# rev_n_v35.net
KiCad netlist of a schematic drawn in EAGLE
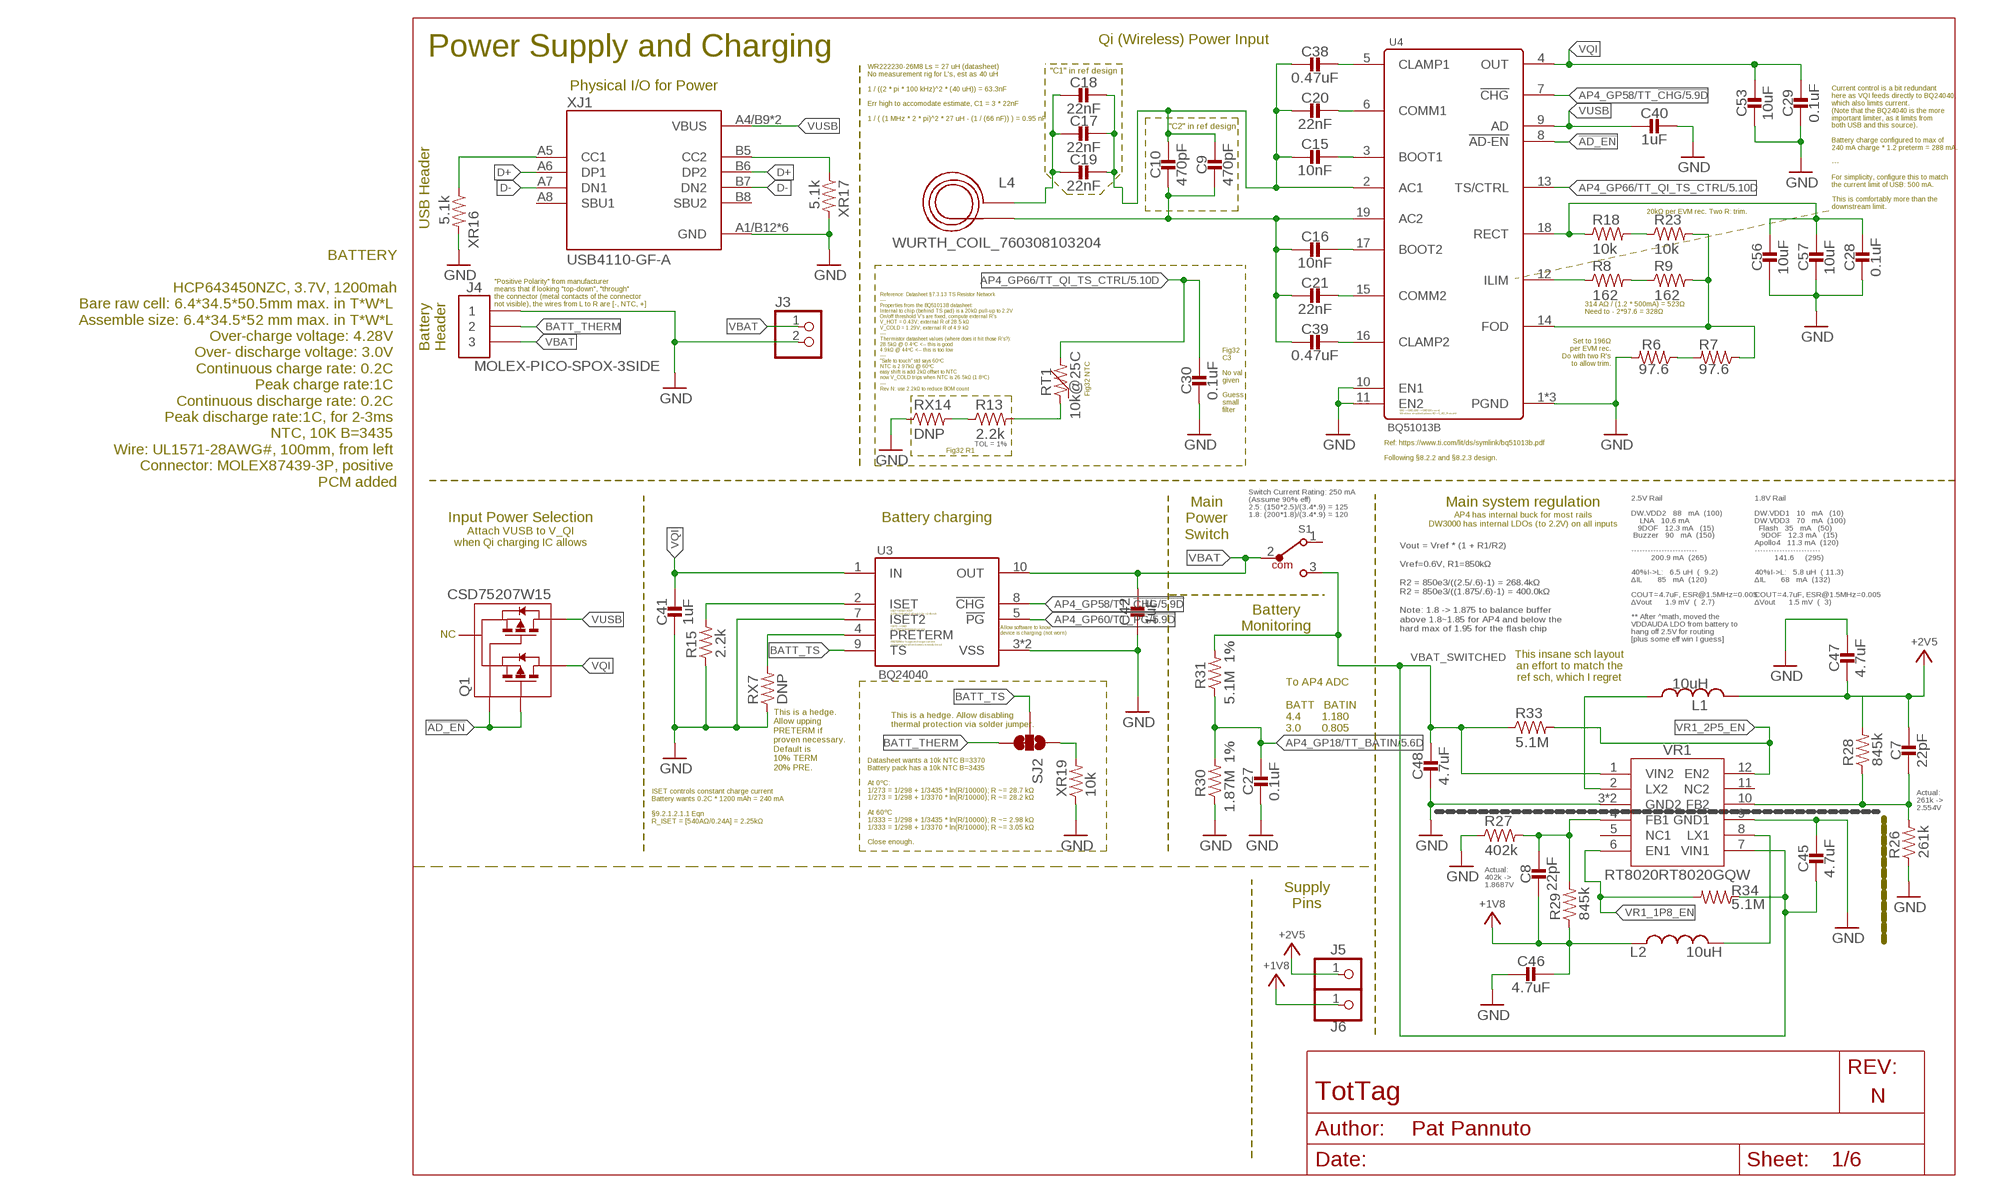
[diagram p0: schematic, sheet 1]
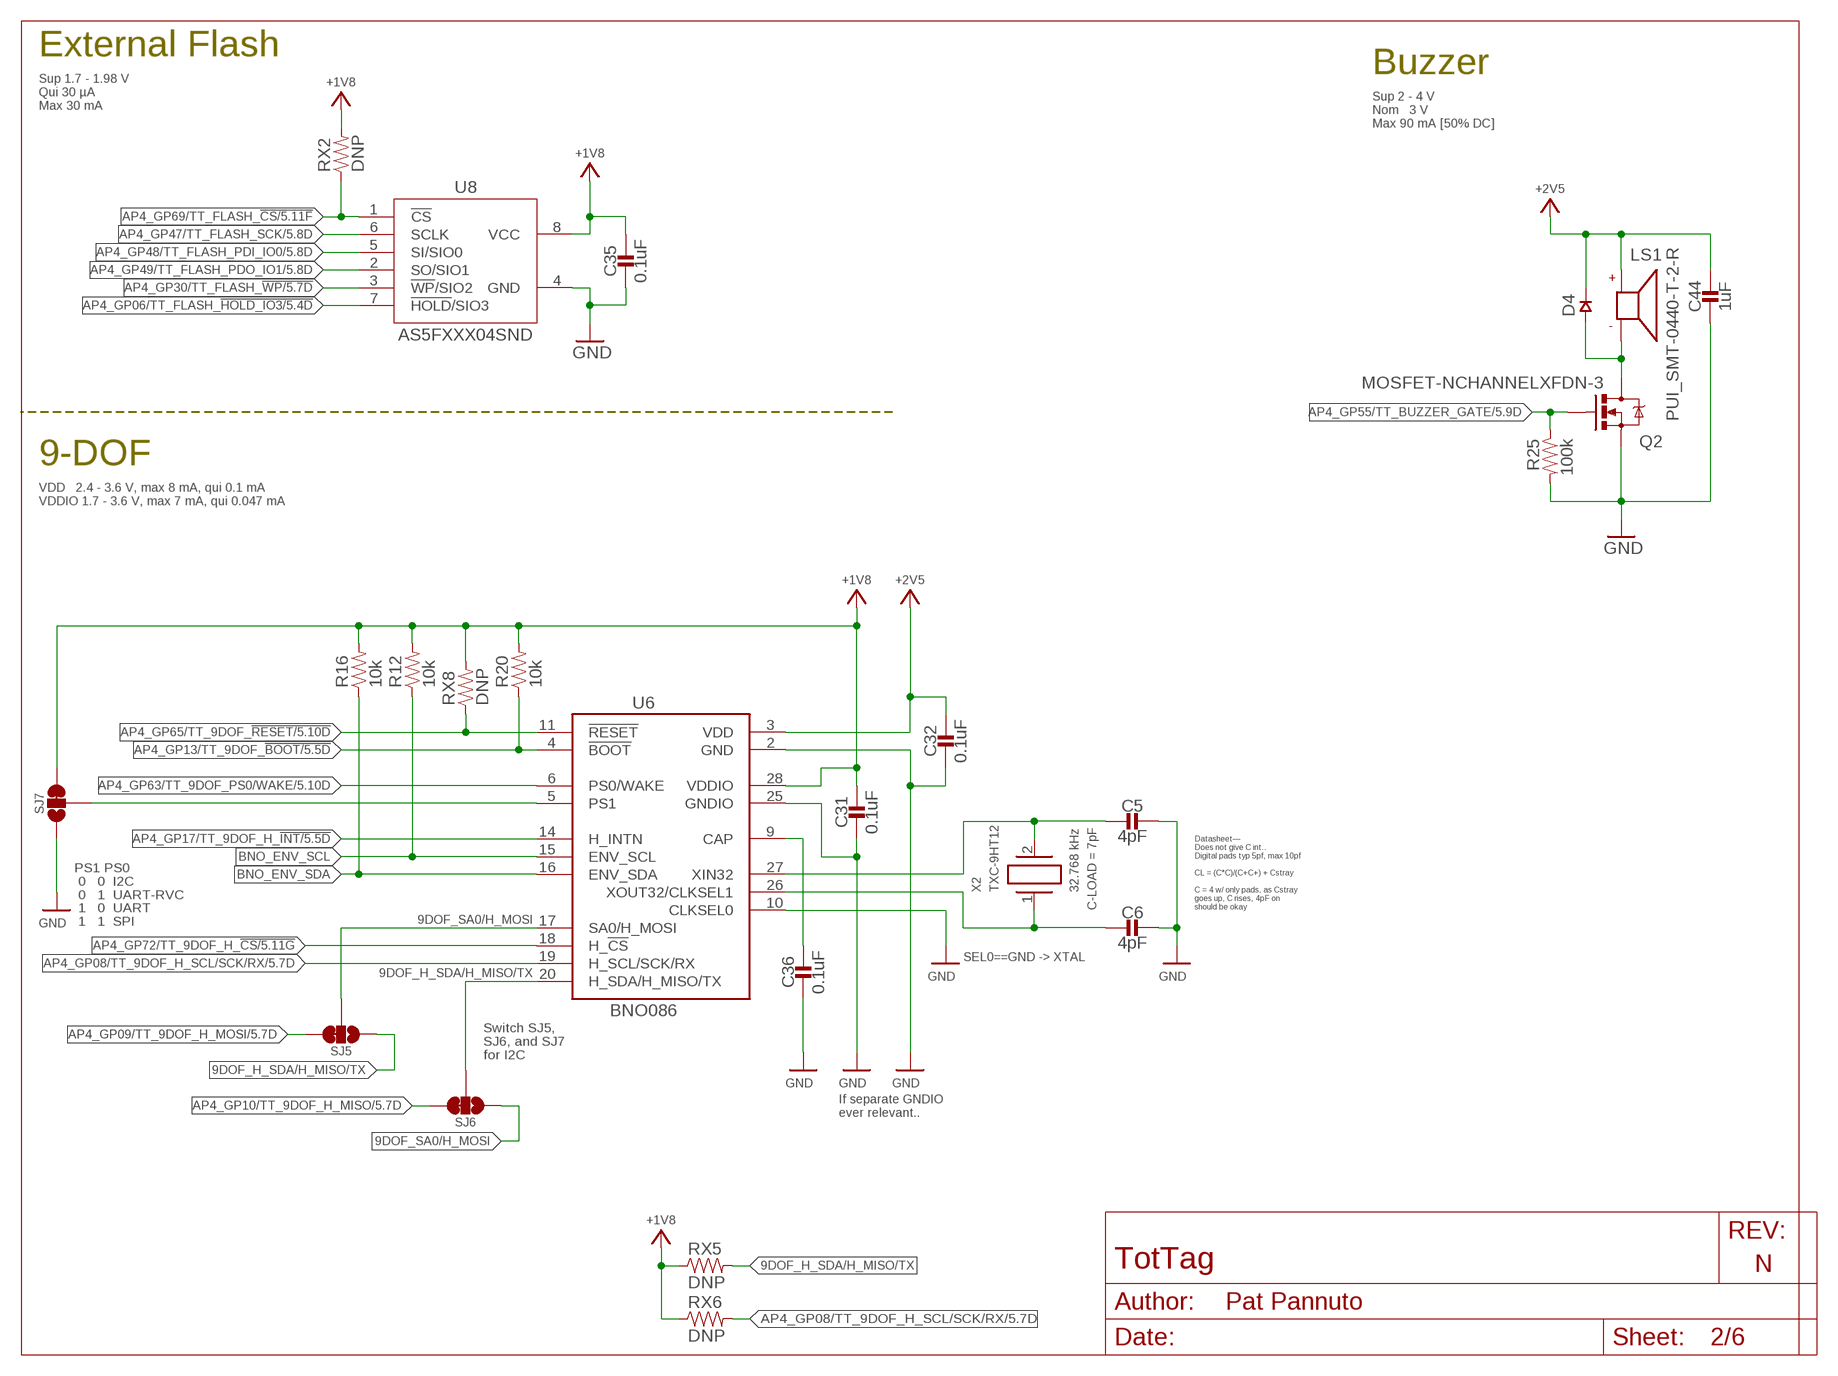
[diagram p1: schematic, sheet 2]
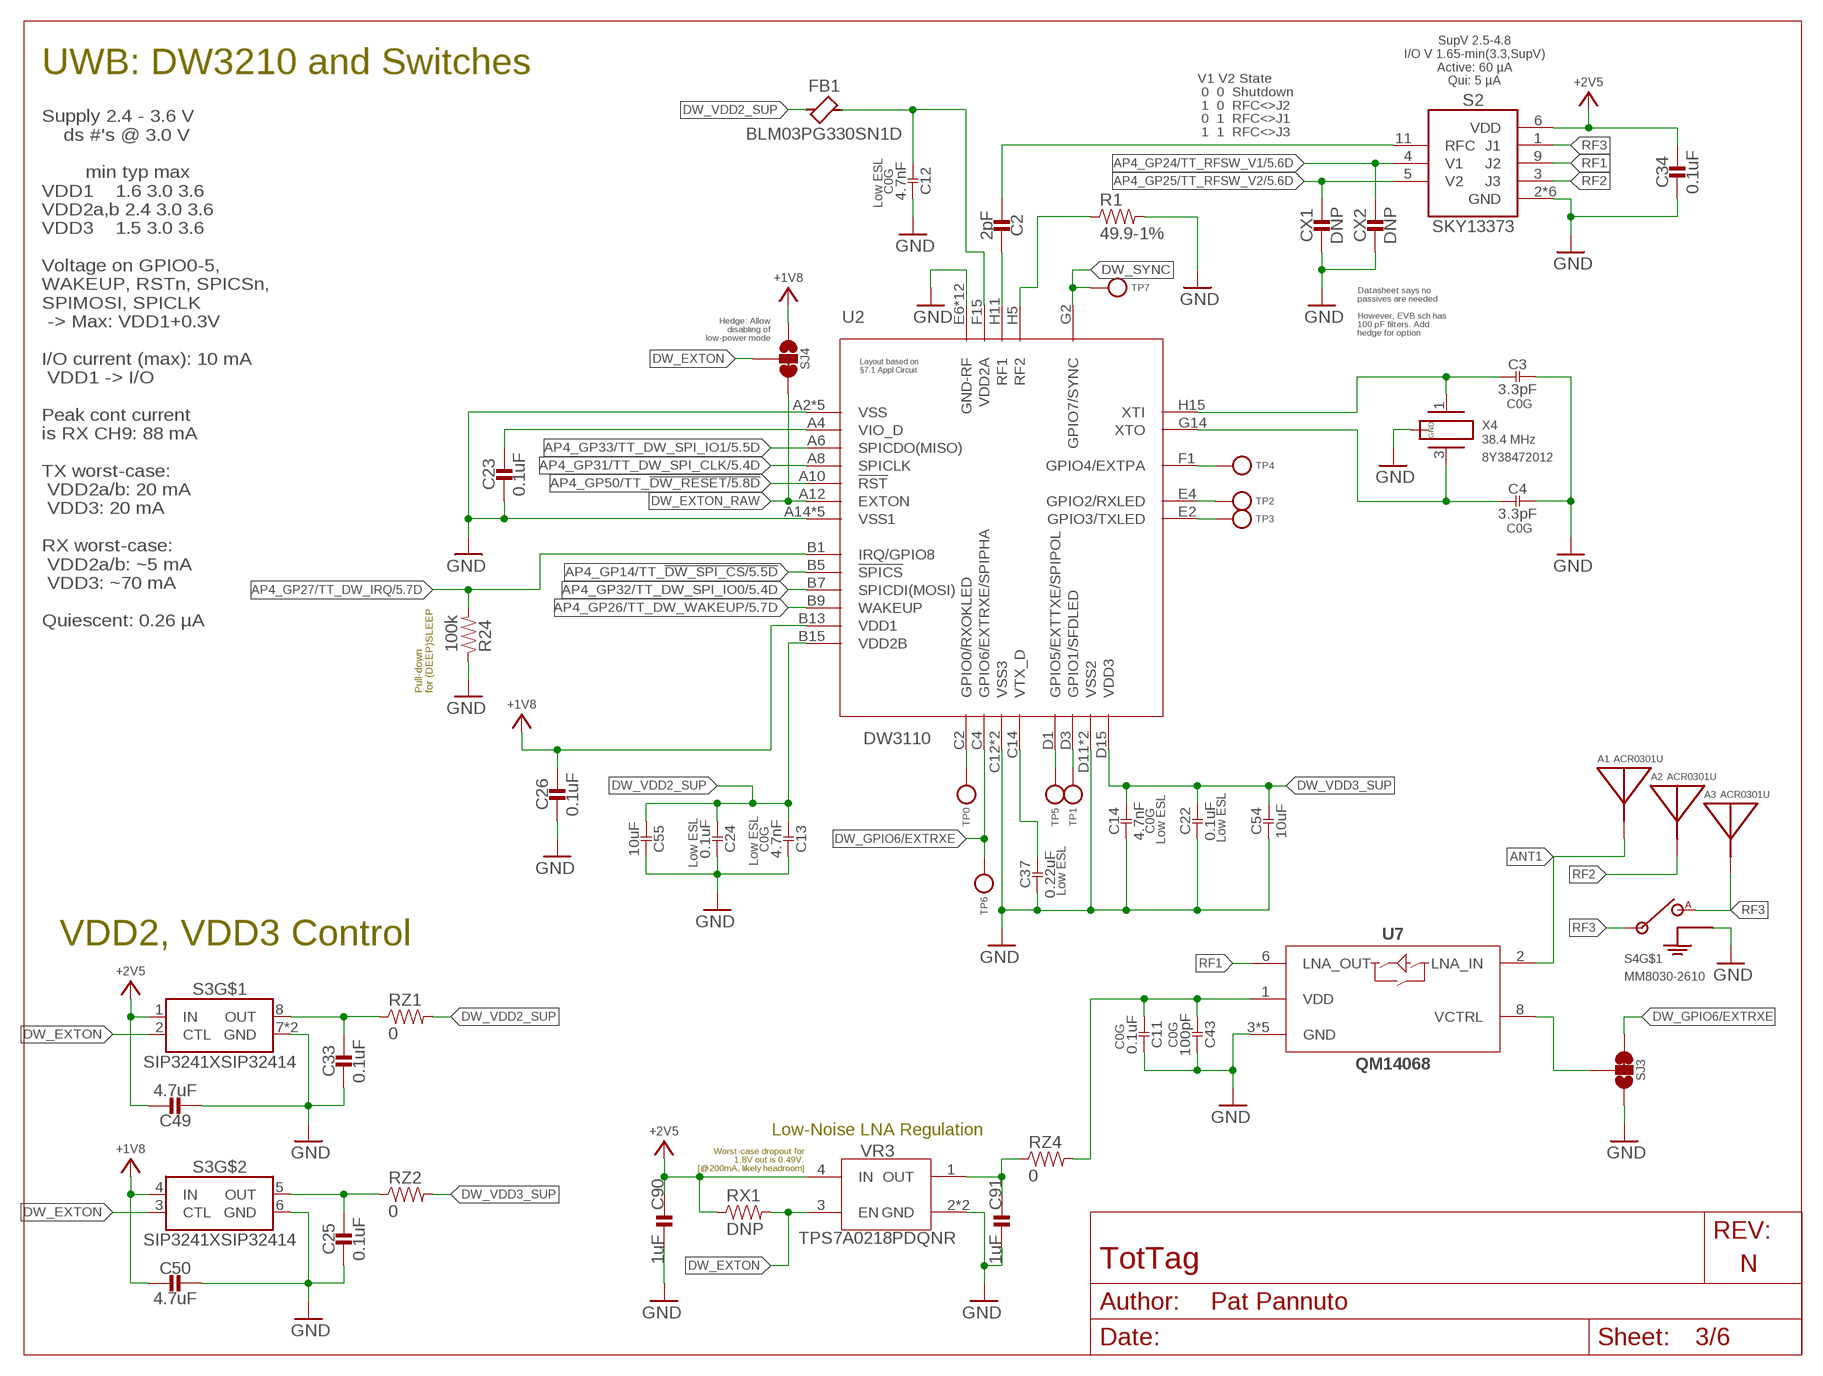
[diagram p2: schematic, sheet 3]
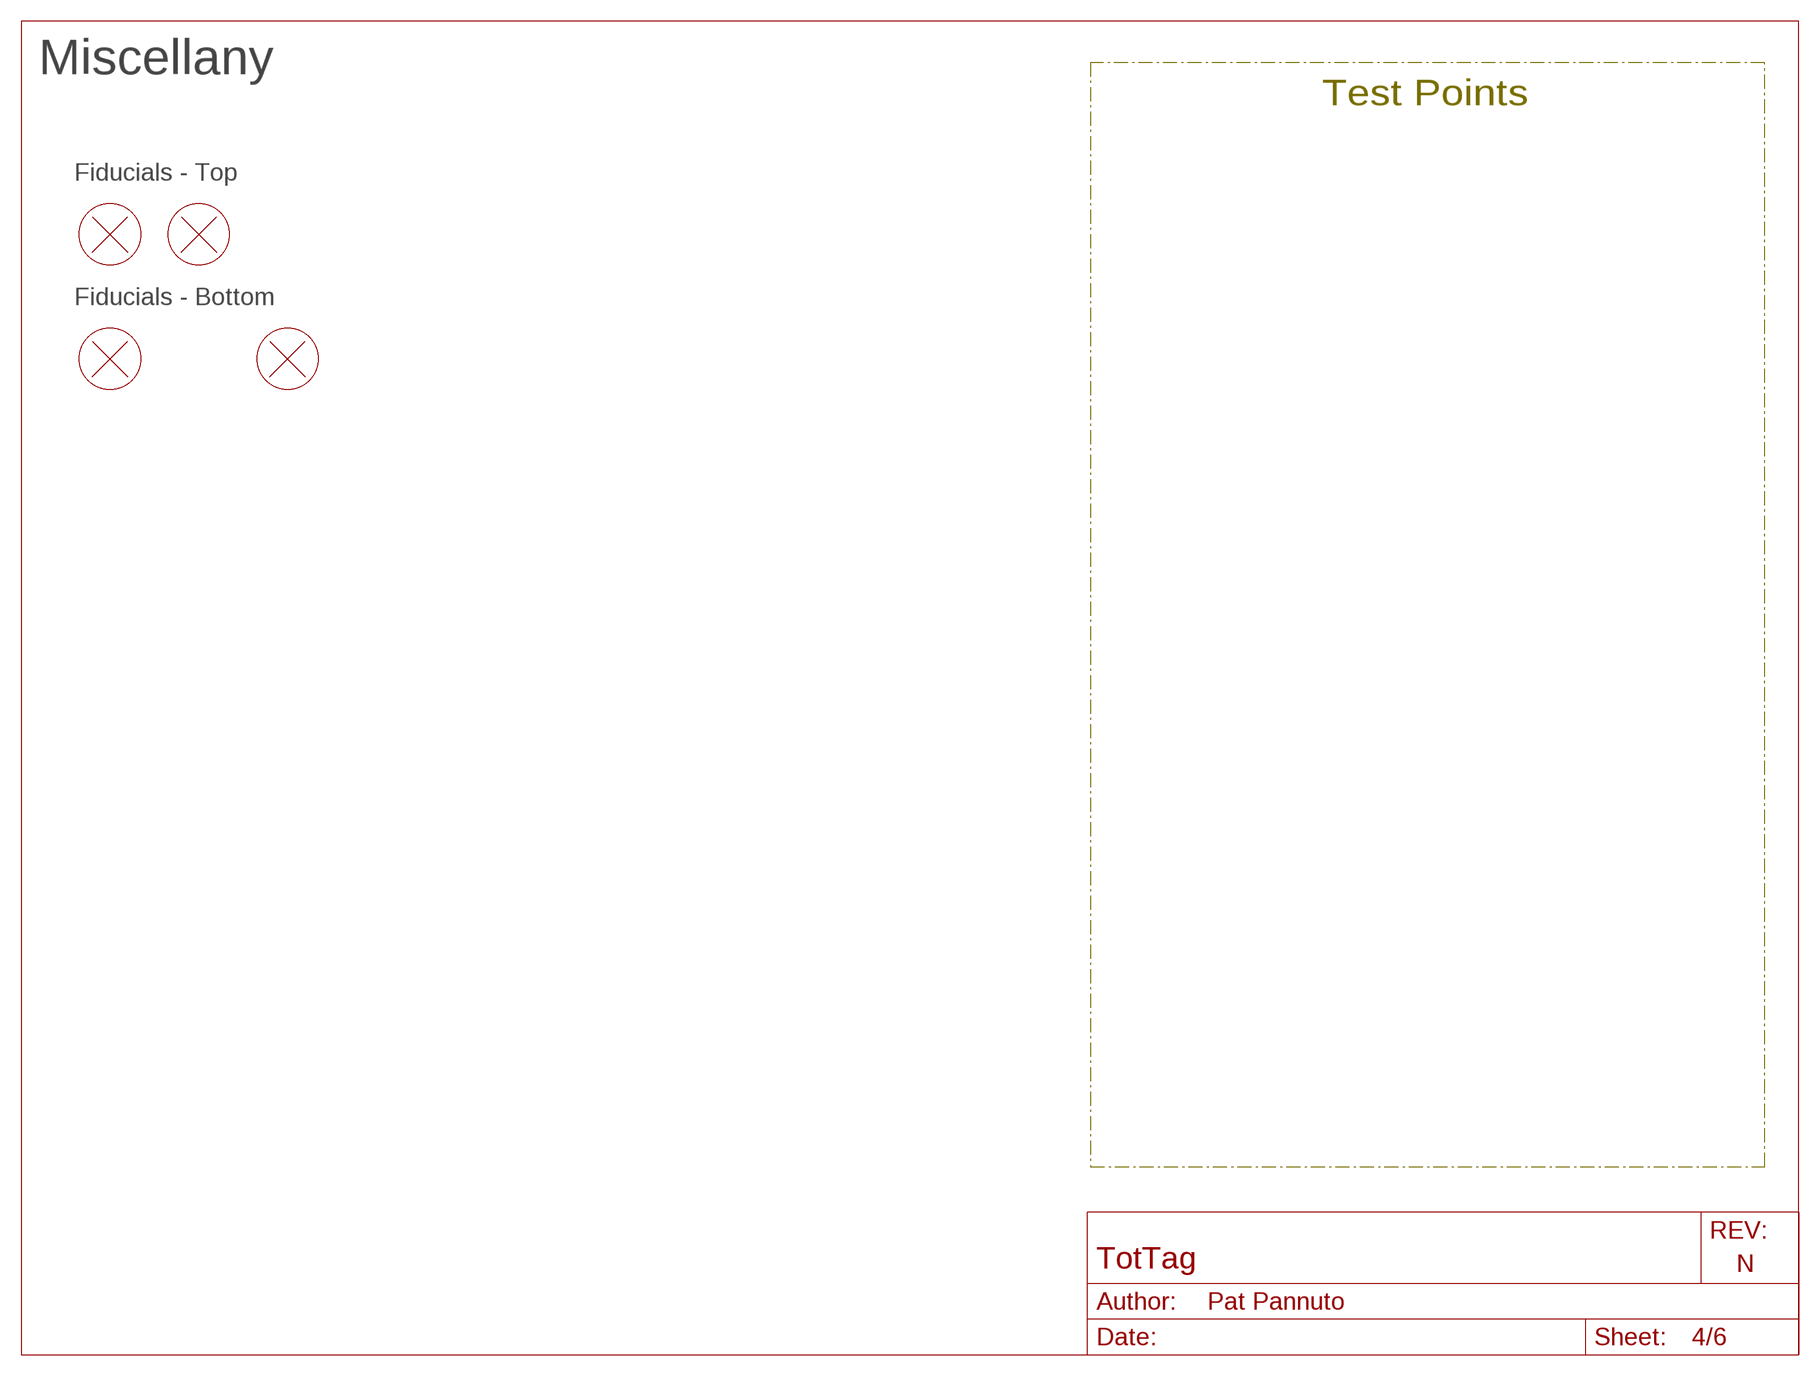
[diagram p3: schematic, sheet 4]
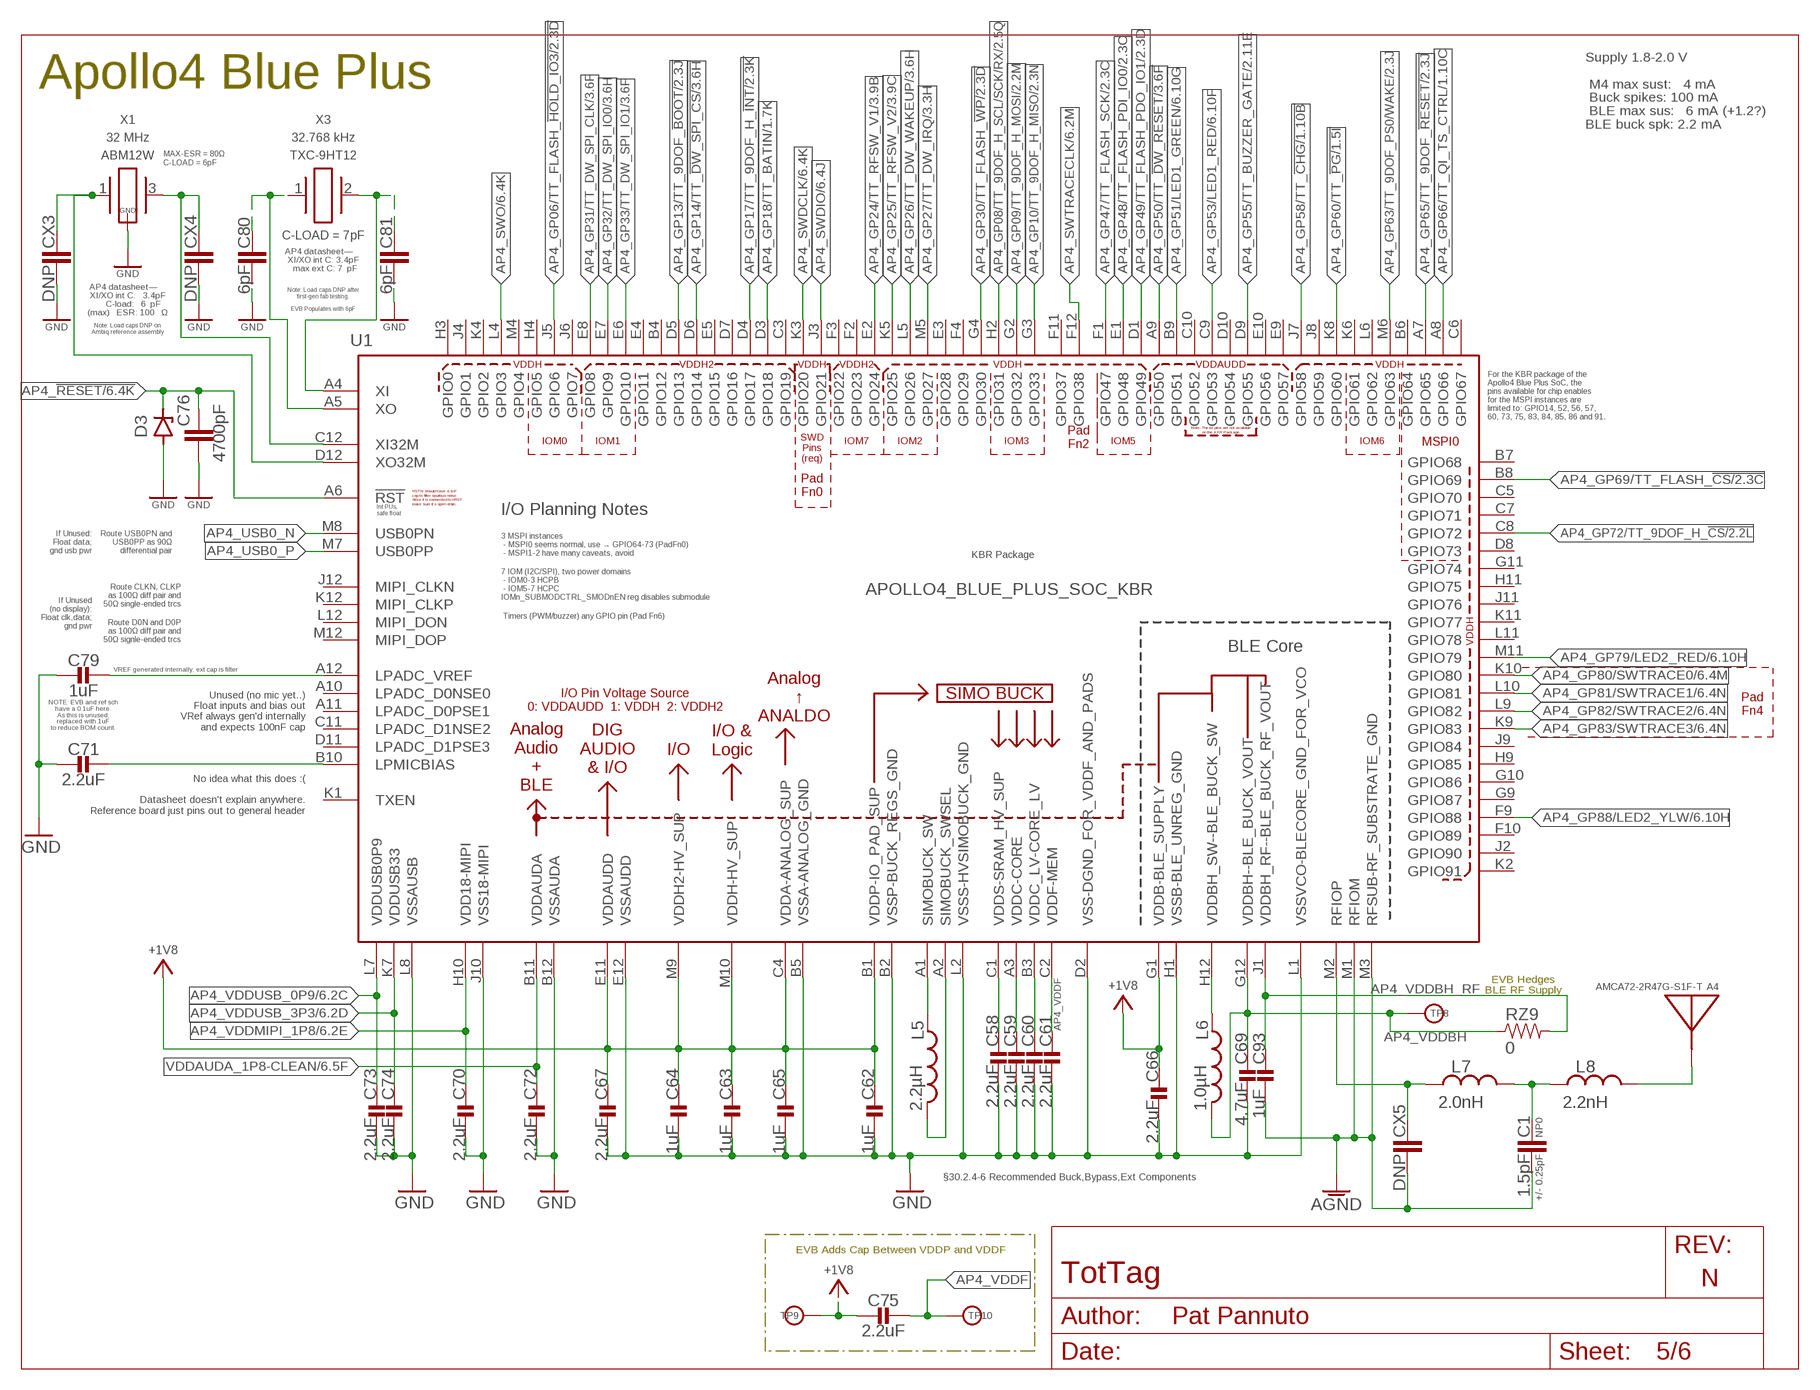
[diagram p4: schematic, sheet 5]
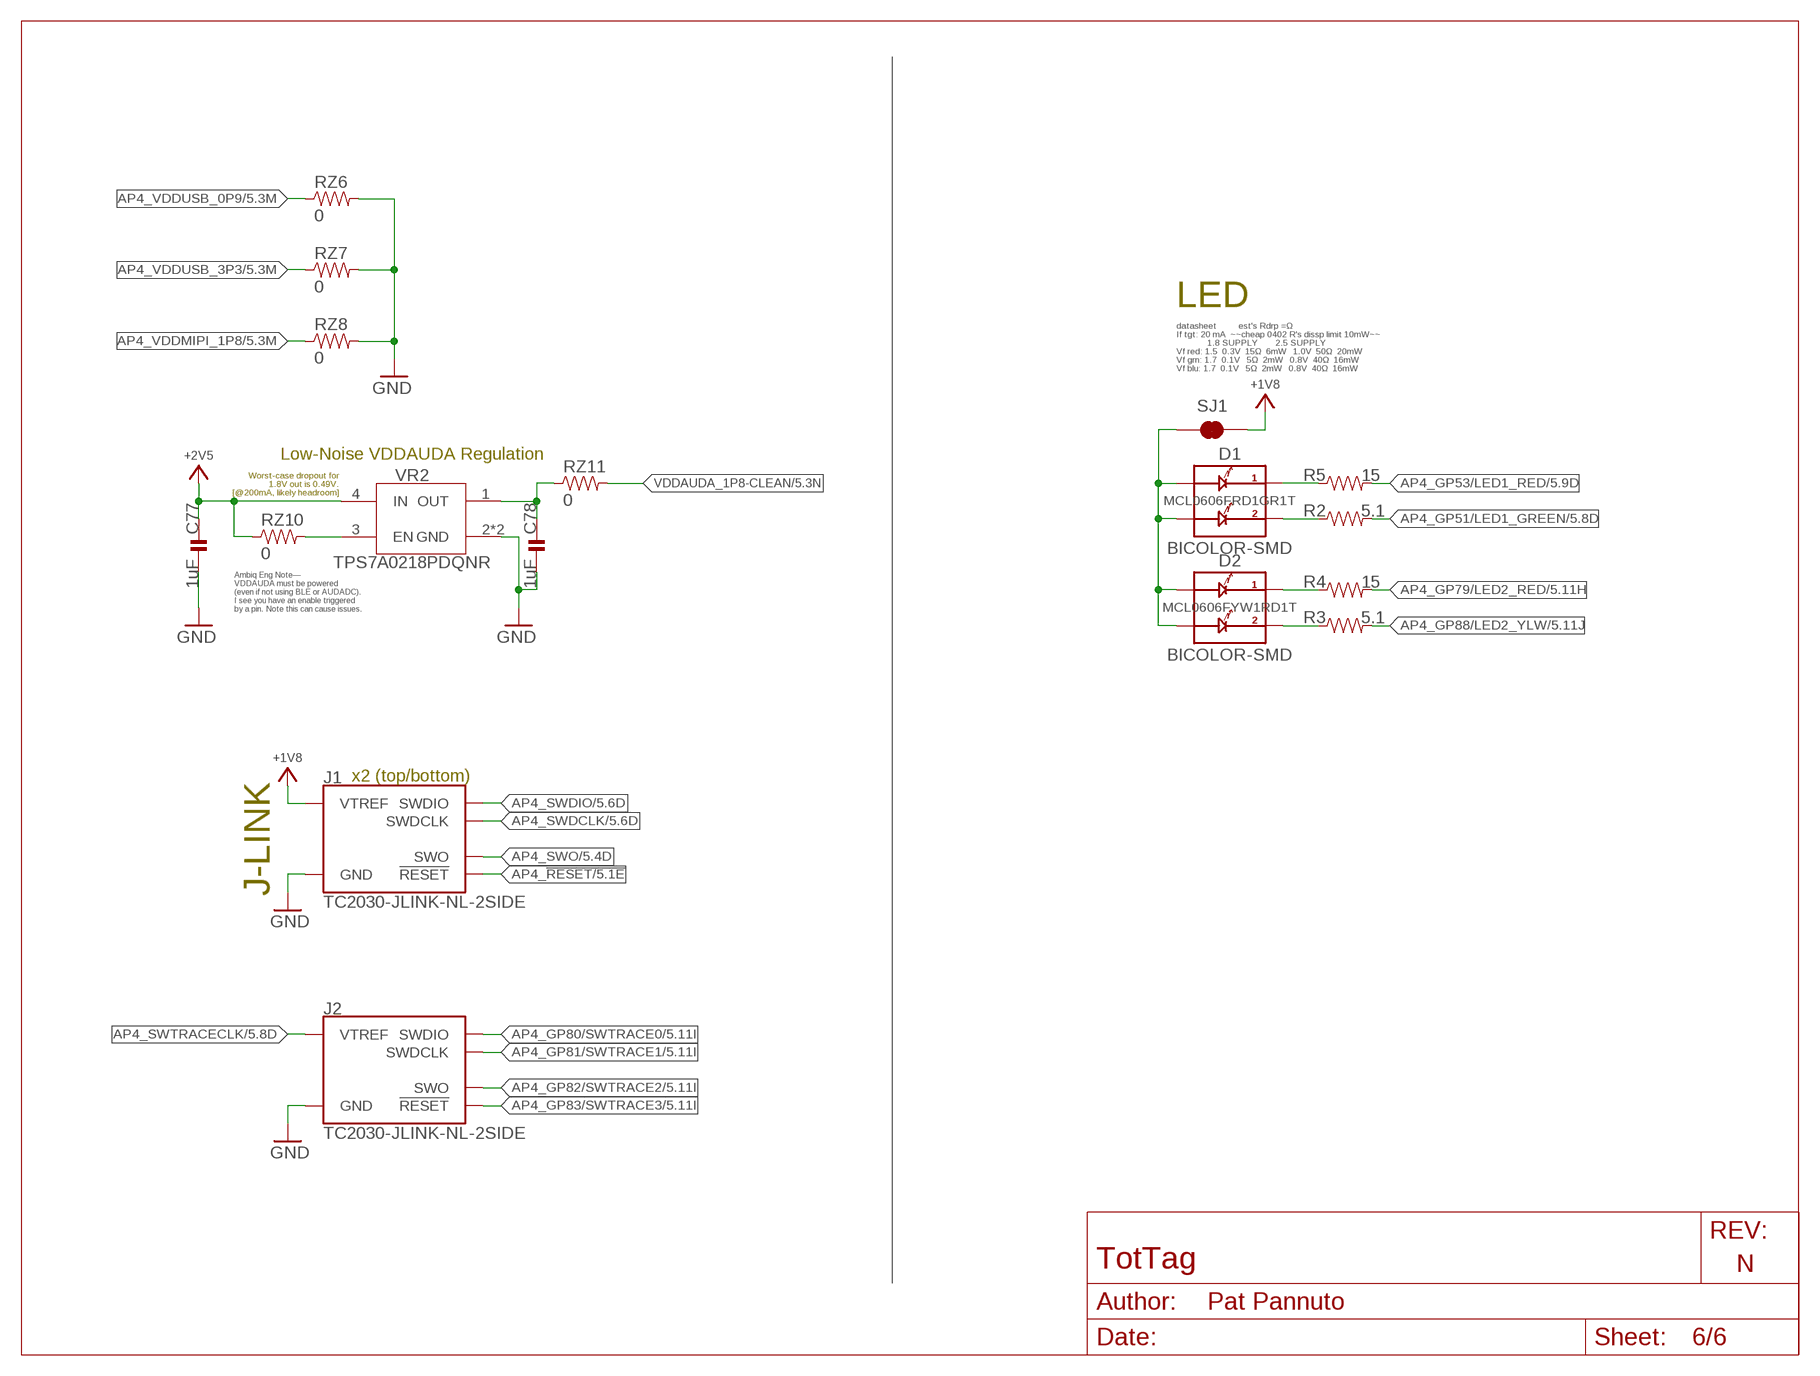
[diagram p5: schematic, sheet 6]

(export (version "E")
  (design (tool "Eeschema 10.0.6"))
  (components
    (comp (ref "C5")
      (value "4pF")
      (footprint "eagle-import:0201_CAP")
      (fields (field (name "MANUFACTURER") "Murata") (field (name "MPN") "GRM0335C1H4R0BA01D"))
      (libsource (lib "eagle-import") (part "passives_20904581_CAPACITOR0201_CAP"))
    )
    (comp (ref "C6")
      (value "4pF")
      (footprint "eagle-import:0201_CAP")
      (fields (field (name "MANUFACTURER") "Murata") (field (name "MPN") "GRM0335C1H4R0BA01D"))
      (libsource (lib "eagle-import") (part "passives_20904581_CAPACITOR0201_CAP"))
    )
    (comp (ref "C31")
      (value "0.1uF")
      (footprint "eagle-import:0402_CAP")
      (fields (field (name "MPN") "CL05A104KP5NNNC"))
      (libsource (lib "eagle-import") (part "passives_20904581_CAPACITOR0402_CAP"))
    )
    (comp (ref "C32")
      (value "0.1uF")
      (footprint "eagle-import:0402_CAP")
      (fields (field (name "MPN") "CL05A104KP5NNNC"))
      (libsource (lib "eagle-import") (part "passives_20904581_CAPACITOR0402_CAP"))
    )
    (comp (ref "C35")
      (value "0.1uF")
      (footprint "eagle-import:0402_CAP")
      (fields (field (name "MPN") "CL05A104KP5NNNC"))
      (libsource (lib "eagle-import") (part "passives_20904581_CAPACITOR0402_CAP"))
    )
    (comp (ref "C36")
      (value "0.1uF")
      (footprint "eagle-import:0402_CAP")
      (fields (field (name "MPN") "CL05A104KP5NNNC"))
      (libsource (lib "eagle-import") (part "CAPACITOR0402_CAP"))
    )
    (comp (ref "C44")
      (value "1uF")
      (footprint "eagle-import:0402_CAP")
      (fields (field (name "MPN") "GRM155R70J105KA12J"))
      (libsource (lib "eagle-import") (part "CAPACITOR0402_CAP"))
    )
    (comp (ref "D4")
      (value "DIODE0402")
      (footprint "eagle-import:0402_DIODE")
      (fields (field (name "MPN") "CDSQR400B-HF"))
      (libsource (lib "eagle-import") (part "DIODE0402"))
    )
    (comp (ref "LS1")
      (value "PUI_SMT-0440-T-2-R")
      (footprint "eagle-import:SMT-0440-T-2-R")
      (fields (field (name "MPN") "SMT-0440-T-2-R"))
      (libsource (lib "eagle-import") (part "PUI_SMT-0440-T-2-R"))
    )
    (comp (ref "Q2")
      (value "MOSFET-NCHANNELXFDN-3")
      (footprint "eagle-import:XFDFN-3")
      (libsource (lib "eagle-import") (part "MOSFET-NCHANNELXFDN-3"))
    )
    (comp (ref "R12")
      (value "10k")
      (footprint "eagle-import:0402_RES")
      (fields (field (name "MPN") "RC0402JR-0710KL"))
      (libsource (lib "eagle-import") (part "RESISTOR0402_RES"))
    )
    (comp (ref "R16")
      (value "10k")
      (footprint "eagle-import:0402_RES")
      (fields (field (name "MPN") "RC0402JR-0710KL"))
      (libsource (lib "eagle-import") (part "RESISTOR0402_RES"))
    )
    (comp (ref "R20")
      (value "10k")
      (footprint "eagle-import:0402_RES")
      (fields (field (name "MPN") "RC0402JR-0710KL"))
      (libsource (lib "eagle-import") (part "RESISTOR0402_RES"))
    )
    (comp (ref "R25")
      (value "100k")
      (footprint "eagle-import:0402_RES")
      (fields (field (name "MPN") "RT0402BRE07100KL"))
      (libsource (lib "eagle-import") (part "RESISTOR0402_RES"))
    )
    (comp (ref "RX2")
      (value "DNP")
      (footprint "eagle-import:0603-RES")
      (libsource (lib "eagle-import") (part "passives_20904581_RESISTOR0603_RES"))
    )
    (comp (ref "RX5")
      (value "DNP")
      (footprint "eagle-import:0603-RES")
      (libsource (lib "eagle-import") (part "passives_20904581_RESISTOR0603_RES"))
    )
    (comp (ref "RX6")
      (value "DNP")
      (footprint "eagle-import:0603-RES")
      (libsource (lib "eagle-import") (part "passives_20904581_RESISTOR0603_RES"))
    )
    (comp (ref "RX8")
      (value "DNP")
      (footprint "eagle-import:0603-RES")
      (libsource (lib "eagle-import") (part "passives_20904581_RESISTOR0603_RES"))
    )
    (comp (ref "SJ5")
      (value "JUMPER-SMT_3_1-NC_TRACE_SILK")
      (footprint "eagle-import:SMT-JUMPER_3_1-NC_TRACE_SILK")
      (libsource (lib "eagle-import") (part "JUMPER-SMT_3_1-NC_TRACE_SILK"))
    )
    (comp (ref "SJ6")
      (value "JUMPER-SMT_3_1-NC_TRACE_SILK")
      (footprint "eagle-import:SMT-JUMPER_3_1-NC_TRACE_SILK")
      (libsource (lib "eagle-import") (part "JUMPER-SMT_3_1-NC_TRACE_SILK"))
    )
    (comp (ref "SJ7")
      (value "JUMPER-SMT_3_1-NC_TRACE_SILK")
      (footprint "eagle-import:SMT-JUMPER_3_1-NC_TRACE_SILK")
      (libsource (lib "eagle-import") (part "JUMPER-SMT_3_1-NC_TRACE_SILK"))
    )
    (comp (ref "U6")
      (value "BNO086")
      (footprint "eagle-import:LGA28R0P510X4_5P2X3P8X1")
      (fields (field (name "MANUFACTURER") "CEVA Technologies, Inc."))
      (libsource (lib "eagle-import") (part "BNO086"))
    )
    (comp (ref "U8")
      (value "AS5FXXX04SND")
      (footprint "eagle-import:AS5FXXXXXXXX-XXLXN")
      (fields (field (name "MANUFACTURER") "Alliance Memory") (field (name "MPN") "AS5F18G04SND-10LIN"))
      (libsource (lib "eagle-import") (part "AS5FXXX04SND"))
    )
    (comp (ref "X2")
      (value "TXC-9HT12")
      (footprint "eagle-import:TXC-9HT12")
      (fields
        (field (name "C-LOAD") "7pF")
        (field (name "FREQUENCY") "32.768 kHz")
        (field (name "MANUFACTURER") "TXC Corp")
        (field (name "MPN") "9HT12-32.768KDZY-T")
      )
      (libsource (lib "eagle-import") (part "TXC-9HT12"))
    )
    (comp (ref "FD1")
      (value "FIDUCIAL")
      (footprint "eagle-import:FIDUCIAL_1MM-CU_2MM-MASK")
      (libsource (lib "eagle-import") (part "FIDUCIAL"))
    )
    (comp (ref "FD2")
      (value "FIDUCIAL")
      (footprint "eagle-import:FIDUCIAL_1MM-CU_2MM-MASK")
      (libsource (lib "eagle-import") (part "FIDUCIAL"))
    )
    (comp (ref "FD4")
      (value "FIDUCIAL")
      (footprint "eagle-import:FIDUCIAL_1MM-CU_2MM-MASK")
      (libsource (lib "eagle-import") (part "FIDUCIAL"))
    )
    (comp (ref "FD6")
      (value "FIDUCIAL")
      (footprint "eagle-import:FIDUCIAL_1MM-CU_2MM-MASK")
      (libsource (lib "eagle-import") (part "FIDUCIAL"))
    )
    (comp (ref "C7")
      (value "22pF")
      (footprint "eagle-import:0201_CAP")
      (fields (field (name "MPN") "GRM0335C1H220FA01D"))
      (libsource (lib "eagle-import") (part "passives_20904581_CAPACITOR0201_CAP"))
    )
    (comp (ref "C8")
      (value "22pF")
      (footprint "eagle-import:0201_CAP")
      (fields (field (name "MPN") "GRM0335C1H220FA01D"))
      (libsource (lib "eagle-import") (part "passives_20904581_CAPACITOR0201_CAP"))
    )
    (comp (ref "C9")
      (value "470pF")
      (footprint "eagle-import:0402_CAP")
      (description "CAP CER 470PF 50V C0G/NP0 0402")
      (fields (field (name "MANUFACTURER") "Murata") (field (name "MPN") "GRM1555C1H471JA01J"))
      (libsource (lib "eagle-import") (part "passives_20904581_CAPACITOR0402_CAP"))
    )
    (comp (ref "C10")
      (value "470pF")
      (footprint "eagle-import:0402_CAP")
      (description "CAP CER 470PF 50V C0G/NP0 0402")
      (fields (field (name "MANUFACTURER") "Murata") (field (name "MPN") "GRM1555C1H471JA01J"))
      (libsource (lib "eagle-import") (part "passives_20904581_CAPACITOR0402_CAP"))
    )
    (comp (ref "C15")
      (value "10nF")
      (footprint "eagle-import:0402_CAP")
      (fields (field (name "MPN") "GRM155R71H103KA88J"))
      (libsource (lib "eagle-import") (part "passives_20904581_CAPACITOR0402_CAP"))
    )
    (comp (ref "C16")
      (value "10nF")
      (footprint "eagle-import:0402_CAP")
      (fields (field (name "MPN") "GRM155R71H103KA88J"))
      (libsource (lib "eagle-import") (part "passives_20904581_CAPACITOR0402_CAP"))
    )
    (comp (ref "C17")
      (value "22nF")
      (footprint "eagle-import:0402_CAP")
      (fields (field (name "MPN") "GRM155R71E223JA61D"))
      (libsource (lib "eagle-import") (part "passives_20904581_CAPACITOR0402_CAP"))
    )
    (comp (ref "C18")
      (value "22nF")
      (footprint "eagle-import:0402_CAP")
      (fields (field (name "MPN") "GRM155R71E223JA61D"))
      (libsource (lib "eagle-import") (part "passives_20904581_CAPACITOR0402_CAP"))
    )
    (comp (ref "C19")
      (value "22nF")
      (footprint "eagle-import:0402_CAP")
      (fields (field (name "MPN") "GRM155R71E223JA61D"))
      (libsource (lib "eagle-import") (part "passives_20904581_CAPACITOR0402_CAP"))
    )
    (comp (ref "C20")
      (value "22nF")
      (footprint "eagle-import:0402_CAP")
      (fields (field (name "MPN") "CC0402ZRY5V8BB223"))
      (libsource (lib "eagle-import") (part "passives_20904581_CAPACITOR0402_CAP"))
    )
    (comp (ref "C21")
      (value "22nF")
      (footprint "eagle-import:0402_CAP")
      (fields (field (name "MPN") "CC0402ZRY5V8BB223"))
      (libsource (lib "eagle-import") (part "passives_20904581_CAPACITOR0402_CAP"))
    )
    (comp (ref "C27")
      (value "0.1uF")
      (footprint "eagle-import:0402_CAP")
      (fields (field (name "MPN") "GRM155R71C104KA88J "))
      (libsource (lib "eagle-import") (part "CAPACITOR0402_CAP"))
    )
    (comp (ref "C28")
      (value "0.1uF")
      (footprint "eagle-import:0402_CAP")
      (fields (field (name "MPN") "GRM155R71C104KA88J "))
      (libsource (lib "eagle-import") (part "CAPACITOR0402_CAP"))
    )
    (comp (ref "C29")
      (value "0.1uF")
      (footprint "eagle-import:0402_CAP")
      (fields (field (name "MPN") "GRM155R71C104KA88J "))
      (libsource (lib "eagle-import") (part "CAPACITOR0402_CAP"))
    )
    (comp (ref "C30")
      (value "0.1uF")
      (footprint "eagle-import:0402_CAP")
      (fields (field (name "MPN") "GRM155R71C104KA88J "))
      (libsource (lib "eagle-import") (part "CAPACITOR0402_CAP"))
    )
    (comp (ref "C38")
      (value "0.47uF")
      (footprint "eagle-import:0402_CAP")
      (fields (field (name "MPN") "GRT155R61E474ME01D"))
      (libsource (lib "eagle-import") (part "passives_20904581_CAPACITOR0402_CAP"))
    )
    (comp (ref "C39")
      (value "0.47uF")
      (footprint "eagle-import:0402_CAP")
      (fields (field (name "MPN") "GRT155R61E474ME01D"))
      (libsource (lib "eagle-import") (part "passives_20904581_CAPACITOR0402_CAP"))
    )
    (comp (ref "C40")
      (value "1uF")
      (footprint "eagle-import:0402_CAP")
      (fields (field (name "MPN") "GRM155R70J105KA12J"))
      (libsource (lib "eagle-import") (part "CAPACITOR0402_CAP"))
    )
    (comp (ref "C41")
      (value "1uF")
      (footprint "eagle-import:0402_CAP")
      (fields (field (name "MPN") "GRM155R70J105KA12J"))
      (libsource (lib "eagle-import") (part "CAPACITOR0402_CAP"))
    )
    (comp (ref "C42")
      (value "1uF")
      (footprint "eagle-import:0402_CAP")
      (fields (field (name "MPN") "GRM155R70J105KA12J"))
      (libsource (lib "eagle-import") (part "CAPACITOR0402_CAP"))
    )
    (comp (ref "C45")
      (value "4.7uF")
      (footprint "eagle-import:0603_CAP")
      (fields (field (name "MPN") "C1608X7S1A475K080AC"))
      (libsource (lib "eagle-import") (part "passives_20904581_CAPACITOR0603_CAP"))
    )
    (comp (ref "C46")
      (value "4.7uF")
      (footprint "eagle-import:0603_CAP")
      (fields (field (name "MPN") "C1608X7S1A475K080AC"))
      (libsource (lib "eagle-import") (part "passives_20904581_CAPACITOR0603_CAP"))
    )
    (comp (ref "C47")
      (value "4.7uF")
      (footprint "eagle-import:0603_CAP")
      (fields (field (name "MPN") "C1608X7S1A475K080AC"))
      (libsource (lib "eagle-import") (part "passives_20904581_CAPACITOR0603_CAP"))
    )
    (comp (ref "C48")
      (value "4.7uF")
      (footprint "eagle-import:0603_CAP")
      (fields (field (name "MPN") "C1608X7S1A475K080AC"))
      (libsource (lib "eagle-import") (part "passives_20904581_CAPACITOR0603_CAP"))
    )
    (comp (ref "C53")
      (value "10uF")
      (footprint "eagle-import:0603_CAP")
      (fields (field (name "MPN") "CM105X5R106M25AT"))
      (libsource (lib "eagle-import") (part "passives_20904581_CAPACITOR0603_CAP"))
    )
    (comp (ref "C56")
      (value "10uF")
      (footprint "eagle-import:0603_CAP")
      (fields (field (name "MPN") "CM105X5R106M25AT"))
      (libsource (lib "eagle-import") (part "passives_20904581_CAPACITOR0603_CAP"))
    )
    (comp (ref "C57")
      (value "10uF")
      (footprint "eagle-import:0603_CAP")
      (fields (field (name "MPN") "CM105X5R106M25AT"))
      (libsource (lib "eagle-import") (part "passives_20904581_CAPACITOR0603_CAP"))
    )
    (comp (ref "J3")
      (value "PINHD-1X2")
      (footprint "eagle-import:1X02")
      (libsource (lib "eagle-import") (part "PINHD-1X2"))
    )
    (comp (ref "J4")
      (value "MOLEX-PICO-SPOX-3SIDE")
      (footprint "eagle-import:MOLEX-PICO-SPOX-3_SIDE")
      (libsource (lib "eagle-import") (part "MOLEX-PICO-SPOX-3SIDE"))
    )
    (comp (ref "J5")
      (value "PINHD-1X1")
      (footprint "eagle-import:1X01")
      (libsource (lib "eagle-import") (part "PINHD-1X1"))
    )
    (comp (ref "J6")
      (value "PINHD-1X1")
      (footprint "eagle-import:1X01")
      (libsource (lib "eagle-import") (part "PINHD-1X1"))
    )
    (comp (ref "L1")
      (value "10uH")
      (footprint "eagle-import:NRX3015")
      (fields (field (name "MANUFACTURER") "TAIYO YUDEN") (field (name "MPN") "NR3015T100M"))
      (libsource (lib "eagle-import") (part "INDUCTORNRX3015"))
    )
    (comp (ref "L2")
      (value "10uH")
      (footprint "eagle-import:NRX3015")
      (fields (field (name "MANUFACTURER") "TAIYO YUDEN") (field (name "MPN") "NR3015T100M"))
      (libsource (lib "eagle-import") (part "INDUCTORNRX3015"))
    )
    (comp (ref "L4")
      (value "WURTH_COIL_760308103204")
      (footprint "eagle-import:WURTH_COIL_760308103204")
      (fields (field (name "MANUFACTURER") "Würth Elektronik") (field (name "MPN") "760308103204"))
      (libsource (lib "eagle-import") (part "WURTH_COIL_760308103204"))
    )
    (comp (ref "Q1")
      (value "CSD75207W15")
      (footprint "eagle-import:DSBGA")
      (fields (field (name "MANUFACTURER") "TEXAS INSTRUMENTS"))
      (libsource (lib "eagle-import") (part "CSD75207W15"))
    )
    (comp (ref "R6")
      (value "97.6")
      (footprint "eagle-import:0402_RES")
      (fields (field (name "MPN") "RMCF0402FT97R6"))
      (libsource (lib "eagle-import") (part "passives_20904581_RESISTOR0402_RES"))
    )
    (comp (ref "R7")
      (value "97.6")
      (footprint "eagle-import:0402_RES")
      (fields (field (name "MPN") "RMCF0402FT97R6"))
      (libsource (lib "eagle-import") (part "passives_20904581_RESISTOR0402_RES"))
    )
    (comp (ref "R8")
      (value "162")
      (footprint "eagle-import:0402_RES")
      (fields (field (name "MPN") "RMCF0402FT162R"))
      (libsource (lib "eagle-import") (part "passives_20904581_RESISTOR0402_RES"))
    )
    (comp (ref "R9")
      (value "162")
      (footprint "eagle-import:0402_RES")
      (fields (field (name "MPN") "RMCF0402FT162R"))
      (libsource (lib "eagle-import") (part "passives_20904581_RESISTOR0402_RES"))
    )
    (comp (ref "R13")
      (value "2.2k")
      (footprint "eagle-import:0402_RES")
      (fields (field (name "MPN") "RC0402FR-072K2L") (field (name "TOL") "1%"))
      (libsource (lib "eagle-import") (part "RESISTOR0402_RES"))
    )
    (comp (ref "R15")
      (value "2.2k")
      (footprint "eagle-import:0402_RES")
      (fields (field (name "MPN") "RC0402FR-072K2L"))
      (libsource (lib "eagle-import") (part "passives_20904581_RESISTOR0402_RES"))
    )
    (comp (ref "R18")
      (value "10k")
      (footprint "eagle-import:0402_RES")
      (fields (field (name "MPN") "RC0402JR-0710KL"))
      (libsource (lib "eagle-import") (part "RESISTOR0402_RES"))
    )
    (comp (ref "R23")
      (value "10k")
      (footprint "eagle-import:0402_RES")
      (fields (field (name "MPN") "RC0402JR-0710KL"))
      (libsource (lib "eagle-import") (part "RESISTOR0402_RES"))
    )
    (comp (ref "R26")
      (value "261k")
      (footprint "eagle-import:0201_RES")
      (fields (field (name "MPN") "ERJ-1GNF2613C"))
      (libsource (lib "eagle-import") (part "passives_20904581_RESISTOR0201_RES"))
    )
    (comp (ref "R27")
      (value "402k")
      (footprint "eagle-import:0201_RES")
      (fields (field (name "MPN") "ERJ-1GNF4023C"))
      (libsource (lib "eagle-import") (part "passives_20904581_RESISTOR0201_RES"))
    )
    (comp (ref "R28")
      (value "845k")
      (footprint "eagle-import:0201_RES")
      (fields (field (name "MPN") "ERJ-1GNF8453C"))
      (libsource (lib "eagle-import") (part "passives_20904581_RESISTOR0201_RES"))
    )
    (comp (ref "R29")
      (value "845k")
      (footprint "eagle-import:0201_RES")
      (fields (field (name "MPN") "ERJ-1GNF8453C"))
      (libsource (lib "eagle-import") (part "passives_20904581_RESISTOR0201_RES"))
    )
    (comp (ref "R30")
      (value "1.87M")
      (footprint "eagle-import:0402_RES")
      (fields (field (name "MPN") "RMCF0402FT1M87") (field (name "TOLERANCE") "1%"))
      (libsource (lib "eagle-import") (part "RESISTOR0402_RES"))
    )
    (comp (ref "R31")
      (value "5.1M")
      (footprint "eagle-import:0402_RES")
      (fields (field (name "MPN") "RMCF0402FT5M10") (field (name "TOLERANCE") "1%"))
      (libsource (lib "eagle-import") (part "RESISTOR0402_RES"))
    )
    (comp (ref "R33")
      (value "5.1M")
      (footprint "eagle-import:0402_RES")
      (fields (field (name "MPN") "RMCF0402FT5M10"))
      (libsource (lib "eagle-import") (part "RESISTOR0402_RES"))
    )
    (comp (ref "R34")
      (value "5.1M")
      (footprint "eagle-import:0402_RES")
      (fields (field (name "MPN") "RMCF0402FT5M10"))
      (libsource (lib "eagle-import") (part "RESISTOR0402_RES"))
    )
    (comp (ref "RT1")
      (value "10k@25C")
      (footprint "eagle-import:0402_RES")
      (fields (field (name "MPN") "NCU15XH103F60RC"))
      (libsource (lib "eagle-import") (part "THERMISTOR0402"))
    )
    (comp (ref "RX7")
      (value "DNP")
      (footprint "eagle-import:0402_RES")
      (libsource (lib "eagle-import") (part "passives_20904581_RESISTOR0402_RES"))
    )
    (comp (ref "RX14")
      (value "DNP")
      (footprint "eagle-import:0402_RES")
      (libsource (lib "eagle-import") (part "RESISTOR0402_RES"))
    )
    (comp (ref "S1")
      (value "450404015514")
      (footprint "eagle-import:450404015514")
      (libsource (lib "eagle-import") (part "450404015514"))
    )
    (comp (ref "SJ2")
      (value "JUMPER-SMT_3_1-NC_TRACE_SILK")
      (footprint "eagle-import:SMT-JUMPER_3_1-NC_TRACE_SILK")
      (libsource (lib "eagle-import") (part "JUMPER-SMT_3_1-NC_TRACE_SILK"))
    )
    (comp (ref "U3")
      (value "BQ24040")
      (footprint "eagle-import:DSQ0010A")
      (fields (field (name "MPN") "BQ24040DSQR"))
      (libsource (lib "eagle-import") (part "BQ24040"))
    )
    (comp (ref "U4")
      (value "BQ51013B")
      (footprint "eagle-import:RHL0020A")
      (fields (field (name "MPN") "BQ51013BRHLR"))
      (libsource (lib "eagle-import") (part "BQ51013B"))
    )
    (comp (ref "VR1")
      (value "RT8020RT8020GQW")
      (footprint "eagle-import:SON45P300X300X80-13T160X250N")
      (fields (field (name "MANUFACTURER") "RichTek") (field (name "MPN") "RT8020GQW"))
      (libsource (lib "eagle-import") (part "RT8020RT8020GQW"))
    )
    (comp (ref "XJ1")
      (value "USB4110-GF-A")
      (footprint "eagle-import:GCT_USB4110-GF-A")
      (fields (field (name "MF") "GCT"))
      (libsource (lib "eagle-import") (part "USB4110-GF-A"))
    )
    (comp (ref "XR16")
      (value "5.1k")
      (footprint "eagle-import:0402_RES")
      (fields (field (name "MPN") "RMCF0402FT5K10"))
      (libsource (lib "eagle-import") (part "passives_20904581_RESISTOR0402_RES"))
    )
    (comp (ref "XR17")
      (value "5.1k")
      (footprint "eagle-import:0402_RES")
      (fields (field (name "MPN") "RMCF0402FT5K10"))
      (libsource (lib "eagle-import") (part "passives_20904581_RESISTOR0402_RES"))
    )
    (comp (ref "XR19")
      (value "10k")
      (footprint "eagle-import:0402_RES")
      (fields (field (name "MPN") "RC0402JR-0710KL"))
      (libsource (lib "eagle-import") (part "RESISTOR0402_RES"))
    )
    (comp (ref "A1")
      (value "ACR0301U")
      (footprint "eagle-import:ACR0301U")
      (fields (field (name "MANUFACTURER") "Abracon"))
      (libsource (lib "eagle-import") (part "ACR0301U"))
    )
    (comp (ref "A2")
      (value "ACR0301U")
      (footprint "eagle-import:ACR0301U")
      (fields (field (name "MANUFACTURER") "Abracon"))
      (libsource (lib "eagle-import") (part "ACR0301U"))
    )
    (comp (ref "A3")
      (value "ACR0301U")
      (footprint "eagle-import:ACR0301U")
      (fields (field (name "MANUFACTURER") "Abracon"))
      (libsource (lib "eagle-import") (part "ACR0301U"))
    )
    (comp (ref "C2")
      (value "2pF")
      (footprint "eagle-import:0201_CAP")
      (fields (field (name "MPN") "CBR02C209A5GAC"))
      (libsource (lib "eagle-import") (part "CAPACITOR0201_CAP"))
    )
    (comp (ref "C3")
      (value "3.3pF")
      (footprint "eagle-import:SMD_2012M-0805US-C")
      (fields
        (field (name "EIA") "C0G")
        (field (name "MANUFACTURER") "KYOCERA AVX")
        (field (name "MPN") "600F3R3BT250XT")
      )
      (libsource (lib "eagle-import") (part "C0805US"))
    )
    (comp (ref "C4")
      (value "3.3pF")
      (footprint "eagle-import:SMD_2012M-0805US-C")
      (fields
        (field (name "EIA") "C0G")
        (field (name "MANUFACTURER") "KYOCERA AVX")
        (field (name "MPN") "600F3R3BT250XT")
      )
      (libsource (lib "eagle-import") (part "C0805US"))
    )
    (comp (ref "C11")
      (value "0.1uF")
      (footprint "eagle-import:SMD_3216M-1206US-C")
      (fields (field (name "EIA") "C0G") (field (name "MPN") "GRM31C5C1H104JA01L"))
      (libsource (lib "eagle-import") (part "C1206US"))
    )
    (comp (ref "C12")
      (value "4.7nF")
      (footprint "eagle-import:SMD_1608M-0603US-C")
      (fields
        (field (name "EIA") "C0G")
        (field (name "FEATURES") "Low ESL")
        (field (name "MANUFACTURER") "KEMET")
        (field (name "MPN") "C0603C472J5GAC7867")
      )
      (libsource (lib "eagle-import") (part "C0603US"))
    )
    (comp (ref "C13")
      (value "4.7nF")
      (footprint "eagle-import:SMD_1608M-0603US-C")
      (fields
        (field (name "EIA") "C0G")
        (field (name "FEATURES") "Low ESL")
        (field (name "MANUFACTURER") "KEMET")
        (field (name "MPN") "C0603C472J5GAC7867")
      )
      (libsource (lib "eagle-import") (part "C0603US"))
    )
    (comp (ref "C14")
      (value "4.7nF")
      (footprint "eagle-import:SMD_1608M-0603US-C")
      (fields
        (field (name "EIA") "C0G")
        (field (name "FEATURES") "Low ESL")
        (field (name "MANUFACTURER") "KEMET")
        (field (name "MPN") "C0603C472J5GAC7867")
      )
      (libsource (lib "eagle-import") (part "C0603US"))
    )
    (comp (ref "C22")
      (value "0.1uF")
      (footprint "eagle-import:SMD_1608M-0603US-C")
      (fields (field (name "FEATURES") "Low ESL") (field (name "MPN") "C1608X7R1H104K080AA"))
      (libsource (lib "eagle-import") (part "C0603US"))
    )
    (comp (ref "C23")
      (value "0.1uF")
      (footprint "eagle-import:0402_CAP")
      (fields (field (name "MPN") "CL05A104KP5NNNC"))
      (libsource (lib "eagle-import") (part "passives_20904581_CAPACITOR0402_CAP"))
    )
    (comp (ref "C24")
      (value "0.1uF")
      (footprint "eagle-import:SMD_1608M-0603US-C")
      (fields (field (name "FEATURES") "Low ESL") (field (name "MPN") "C1608X7R1H104K080AA"))
      (libsource (lib "eagle-import") (part "C0603US"))
    )
    (comp (ref "C25")
      (value "0.1uF")
      (footprint "eagle-import:0402_CAP")
      (fields (field (name "MPN") "CL05A104KP5NNNC"))
      (libsource (lib "eagle-import") (part "passives_20904581_CAPACITOR0402_CAP"))
    )
    (comp (ref "C26")
      (value "0.1uF")
      (footprint "eagle-import:0402_CAP")
      (fields (field (name "MPN") "CL05A104KP5NNNC"))
      (libsource (lib "eagle-import") (part "passives_20904581_CAPACITOR0402_CAP"))
    )
    (comp (ref "C33")
      (value "0.1uF")
      (footprint "eagle-import:0402_CAP")
      (fields (field (name "MPN") "CL05A104KP5NNNC"))
      (libsource (lib "eagle-import") (part "passives_20904581_CAPACITOR0402_CAP"))
    )
    (comp (ref "C34")
      (value "0.1uF")
      (footprint "eagle-import:0402_CAP")
      (fields (field (name "MPN") "CL05A104KP5NNNC"))
      (libsource (lib "eagle-import") (part "passives_20904581_CAPACITOR0402_CAP"))
    )
    (comp (ref "C37")
      (value "0.22uF")
      (footprint "eagle-import:SMD_1608M-0603US-C")
      (fields (field (name "FEATURES") "Low ESL") (field (name "MPN") "C1608X7R1H224K080AB"))
      (libsource (lib "eagle-import") (part "C0603US"))
    )
    (comp (ref "C43")
      (value "100pF")
      (footprint "eagle-import:SMD_1005M-0402US-C")
      (fields (field (name "EIA") "C0G") (field (name "MPN") "C0402C101J3GACTU"))
      (libsource (lib "eagle-import") (part "C0402US"))
    )
    (comp (ref "C49")
      (value "4.7uF")
      (footprint "eagle-import:0603_CAP")
      (fields (field (name "MPN") "C1608X7S1A475K080AC"))
      (libsource (lib "eagle-import") (part "passives_20904581_CAPACITOR0603_CAP"))
    )
    (comp (ref "C50")
      (value "4.7uF")
      (footprint "eagle-import:0603_CAP")
      (fields (field (name "MPN") "C1608X7S1A475K080AC"))
      (libsource (lib "eagle-import") (part "passives_20904581_CAPACITOR0603_CAP"))
    )
    (comp (ref "C54")
      (value "10uF")
      (footprint "eagle-import:SMD_1608M-0603US-C")
      (fields (field (name "MPN") "CM105X5R106M25AT"))
      (libsource (lib "eagle-import") (part "C0603US"))
    )
    (comp (ref "C55")
      (value "10uF")
      (footprint "eagle-import:SMD_1608M-0603US-C")
      (fields (field (name "MPN") "CM105X5R106M25AT"))
      (libsource (lib "eagle-import") (part "C0603US"))
    )
    (comp (ref "C90")
      (value "1uF")
      (footprint "eagle-import:0201_CAP")
      (fields (field (name "MANUFACTURER") "Murata") (field (name "MPN") "GRM033R61A105ME44D"))
      (libsource (lib "eagle-import") (part "passives_20904581_CAPACITOR0201_CAP"))
    )
    (comp (ref "C91")
      (value "1uF")
      (footprint "eagle-import:0201_CAP")
      (fields (field (name "MANUFACTURER") "Murata") (field (name "MPN") "GRM033R61A105ME44D"))
      (libsource (lib "eagle-import") (part "passives_20904581_CAPACITOR0201_CAP"))
    )
    (comp (ref "CX1")
      (value "DNP")
      (footprint "eagle-import:0603_CAP")
      (libsource (lib "eagle-import") (part "passives_20904581_CAPACITOR0603_CAP"))
    )
    (comp (ref "CX2")
      (value "DNP")
      (footprint "eagle-import:0603_CAP")
      (libsource (lib "eagle-import") (part "passives_20904581_CAPACITOR0603_CAP"))
    )
    (comp (ref "FB1")
      (value "BLM03PG330SN1D")
      (footprint "eagle-import:0201_FB")
      (fields (field (name "MANUFACTURER") "Murata"))
      (libsource (lib "eagle-import") (part "FERRITE_BEAD0201"))
    )
    (comp (ref "R1")
      (value "49.9-1%")
      (footprint "eagle-import:0201_RES")
      (fields (field (name "MPN") "ERJ-1GNF49R9C"))
      (libsource (lib "eagle-import") (part "passives_20904581_RESISTOR0201_RES"))
    )
    (comp (ref "R24")
      (value "100k")
      (footprint "eagle-import:0402_RES")
      (fields (field (name "MPN") "RT0402BRE07100KL"))
      (libsource (lib "eagle-import") (part "RESISTOR0402_RES"))
    )
    (comp (ref "RX1")
      (value "DNP")
      (footprint "eagle-import:0603-RES")
      (libsource (lib "eagle-import") (part "passives_20904581_RESISTOR0603_RES"))
    )
    (comp (ref "RZ1")
      (value "0")
      (footprint "eagle-import:0603-RES")
      (fields (field (name "MPN") "RMCF0603ZT0R00"))
      (libsource (lib "eagle-import") (part "passives_20904581_RESISTOR0603_RES"))
    )
    (comp (ref "RZ2")
      (value "0")
      (footprint "eagle-import:0603-RES")
      (fields (field (name "MPN") "RMCF0603ZT0R00"))
      (libsource (lib "eagle-import") (part "passives_20904581_RESISTOR0603_RES"))
    )
    (comp (ref "RZ4")
      (value "0")
      (footprint "eagle-import:0402_RES")
      (fields (field (name "MPN") "RMCF0402ZT0R00"))
      (libsource (lib "eagle-import") (part "passives_20904581_RESISTOR0402_RES"))
    )
    (comp (ref "S2")
      (value "SKY13373")
      (footprint "eagle-import:SKY13373")
      (fields (field (name "MANUFACTURER") "Skyworks") (field (name "MPN") "SKY13373-460LF"))
      (libsource (lib "eagle-import") (part "SKY13373"))
    )
    (comp (ref "S3")
      (value "SIP3241XSIP32414")
      (footprint "eagle-import:TDFN2X2X0P6-8")
      (fields (field (name "MANUFACTURER") "Vishay") (field (name "MPN") "SIP32414DNP-T1-GE4"))
      (libsource (lib "eagle-import") (part "SIP3241XSIP32414"))
    )
    (comp (ref "S4")
      (value "MM8030-2610")
      (footprint "eagle-import:MM8030-2610")
      (fields (field (name "MANUFACTURER") "Murata"))
      (libsource (lib "eagle-import") (part "MM8030-2610"))
    )
    (comp (ref "SJ3")
      (value "JUMPER-SMT_3_1-NC_TRACE_SILK")
      (footprint "eagle-import:SMT-JUMPER_3_1-NC_TRACE_SILK")
      (libsource (lib "eagle-import") (part "JUMPER-SMT_3_1-NC_TRACE_SILK"))
    )
    (comp (ref "SJ4")
      (value "JUMPER-SMT_3_1-NC_TRACE_SILK")
      (footprint "eagle-import:SMT-JUMPER_3_1-NC_TRACE_SILK")
      (libsource (lib "eagle-import") (part "JUMPER-SMT_3_1-NC_TRACE_SILK"))
    )
    (comp (ref "TP0")
      (value "TEST-POINT")
      (footprint "eagle-import:PAD.03X.03")
      (libsource (lib "eagle-import") (part "TEST-POINT"))
    )
    (comp (ref "TP1")
      (value "TEST-POINT")
      (footprint "eagle-import:PAD.03X.03")
      (libsource (lib "eagle-import") (part "TEST-POINT"))
    )
    (comp (ref "TP2")
      (value "TEST-POINT")
      (footprint "eagle-import:PAD.03X.03")
      (libsource (lib "eagle-import") (part "TEST-POINT"))
    )
    (comp (ref "TP3")
      (value "TEST-POINT")
      (footprint "eagle-import:PAD.03X.03")
      (libsource (lib "eagle-import") (part "TEST-POINT"))
    )
    (comp (ref "TP4")
      (value "TEST-POINT")
      (footprint "eagle-import:PAD.03X.03")
      (libsource (lib "eagle-import") (part "TEST-POINT"))
    )
    (comp (ref "TP5")
      (value "TEST-POINT")
      (footprint "eagle-import:PAD.03X.03")
      (libsource (lib "eagle-import") (part "TEST-POINT"))
    )
    (comp (ref "TP6")
      (value "TEST-POINT")
      (footprint "eagle-import:PAD.03X.03")
      (libsource (lib "eagle-import") (part "TEST-POINT"))
    )
    (comp (ref "TP7")
      (value "TEST-POINT")
      (footprint "eagle-import:PAD.03X.03")
      (libsource (lib "eagle-import") (part "TEST-POINT"))
    )
    (comp (ref "U2")
      (value "DW3110")
      (footprint "eagle-import:WLCSP52")
      (fields (field (name "MANUFACTURER") "Qorvo"))
      (libsource (lib "eagle-import") (part "DW3110"))
    )
    (comp (ref "U7")
      (value "QM14068")
      (footprint "eagle-import:QM14068")
      (fields (field (name "MANUFACTURER") "Qorvo"))
      (libsource (lib "eagle-import") (part "QM14068"))
    )
    (comp (ref "VR3")
      (value "TPS7A0218PDQNR")
      (footprint "eagle-import:4-XDFN-EP")
      (libsource (lib "eagle-import") (part "TPS7A0218PDQNR"))
    )
    (comp (ref "X4")
      (value "TXC-8Y")
      (footprint "eagle-import:TXC-8Y")
      (fields
        (field (name "FREQ") "38.4 MHz")
        (field (name "MANUFACTURER") "TXC")
        (field (name "MPN") "8Y38472012")
      )
      (libsource (lib "eagle-import") (part "TXC-8Y"))
    )
    (comp (ref "A4")
      (value "AMCA72-2R47G-S1F-T")
      (footprint "eagle-import:AMCA72-2R470G-S1F-T")
      (fields (field (name "MPN") "AMCA72-2R470G-S1F-T4"))
      (libsource (lib "eagle-import") (part "AMCA72-2R47G-S1F-T"))
    )
    (comp (ref "C1")
      (value "1.5pF")
      (footprint "eagle-import:CAPC1005X60")
      (description "CAP CER 1.5PF 50V C0G/NP0 0402")
      (fields
        (field (name "MANUFACTURER") "KEMET")
        (field (name "MPN") "C0402C159C5GACTU")
        (field (name "TEMPCOEFF") "NP0")
        (field (name "TOLERANCE") "+/- 0.25pF")
      )
      (libsource (lib "eagle-import") (part "CCHIP-0402(1005-METRIC)_"))
    )
    (comp (ref "C58")
      (value "2.2uF")
      (footprint "eagle-import:0201_CAP")
      (fields (field (name "MANUFACTURER") "Murata") (field (name "MPN") "GRM033R61A225KE47D"))
      (libsource (lib "eagle-import") (part "passives_20904581_CAPACITOR0201_CAP"))
    )
    (comp (ref "C59")
      (value "2.2uF")
      (footprint "eagle-import:0201_CAP")
      (fields (field (name "MANUFACTURER") "Murata") (field (name "MPN") "GRM033R61A225KE47D"))
      (libsource (lib "eagle-import") (part "passives_20904581_CAPACITOR0201_CAP"))
    )
    (comp (ref "C60")
      (value "2.2uF")
      (footprint "eagle-import:0201_CAP")
      (fields (field (name "MANUFACTURER") "Murata") (field (name "MPN") "GRM033R61A225KE47D"))
      (libsource (lib "eagle-import") (part "passives_20904581_CAPACITOR0201_CAP"))
    )
    (comp (ref "C61")
      (value "2.2uF")
      (footprint "eagle-import:0201_CAP")
      (fields (field (name "MANUFACTURER") "Murata") (field (name "MPN") "GRM033R61A225KE47D"))
      (libsource (lib "eagle-import") (part "passives_20904581_CAPACITOR0201_CAP"))
    )
    (comp (ref "C62")
      (value "1uF")
      (footprint "eagle-import:0201_CAP")
      (fields (field (name "MANUFACTURER") "Murata") (field (name "MPN") "GRM033R61A105ME44D"))
      (libsource (lib "eagle-import") (part "passives_20904581_CAPACITOR0201_CAP"))
    )
    (comp (ref "C63")
      (value "1uF")
      (footprint "eagle-import:0201_CAP")
      (fields (field (name "MANUFACTURER") "Murata") (field (name "MPN") "GRM033R61A105ME44D"))
      (libsource (lib "eagle-import") (part "passives_20904581_CAPACITOR0201_CAP"))
    )
    (comp (ref "C64")
      (value "1uF")
      (footprint "eagle-import:0201_CAP")
      (fields (field (name "MANUFACTURER") "Murata") (field (name "MPN") "GRM033R61A105ME44D"))
      (libsource (lib "eagle-import") (part "passives_20904581_CAPACITOR0201_CAP"))
    )
    (comp (ref "C65")
      (value "1uF")
      (footprint "eagle-import:0201_CAP")
      (fields (field (name "MANUFACTURER") "Murata") (field (name "MPN") "GRM033R61A105ME44D"))
      (libsource (lib "eagle-import") (part "passives_20904581_CAPACITOR0201_CAP"))
    )
    (comp (ref "C66")
      (value "2.2uF")
      (footprint "eagle-import:0201_CAP")
      (fields (field (name "MANUFACTURER") "Murata") (field (name "MPN") "GRM033R61A225KE47D"))
      (libsource (lib "eagle-import") (part "passives_20904581_CAPACITOR0201_CAP"))
    )
    (comp (ref "C67")
      (value "2.2uF")
      (footprint "eagle-import:0201_CAP")
      (fields (field (name "MANUFACTURER") "Murata") (field (name "MPN") "GRM033R61A225KE47D"))
      (libsource (lib "eagle-import") (part "passives_20904581_CAPACITOR0201_CAP"))
    )
    (comp (ref "C69")
      (value "4.7uF")
      (footprint "eagle-import:0402_CAP")
      (fields (field (name "MPN") "CL05A475MP5NRNC"))
      (libsource (lib "eagle-import") (part "CAPACITOR0402_CAP"))
    )
    (comp (ref "C70")
      (value "2.2uF")
      (footprint "eagle-import:0201_CAP")
      (fields (field (name "MANUFACTURER") "Murata") (field (name "MPN") "GRM033R61A225KE47D"))
      (libsource (lib "eagle-import") (part "passives_20904581_CAPACITOR0201_CAP"))
    )
    (comp (ref "C71")
      (value "2.2uF")
      (footprint "eagle-import:0201_CAP")
      (fields (field (name "MANUFACTURER") "Murata") (field (name "MPN") "GRM033R61A225KE47D"))
      (libsource (lib "eagle-import") (part "passives_20904581_CAPACITOR0201_CAP"))
    )
    (comp (ref "C72")
      (value "2.2uF")
      (footprint "eagle-import:0201_CAP")
      (fields (field (name "MANUFACTURER") "Murata") (field (name "MPN") "GRM033R61A225KE47D"))
      (libsource (lib "eagle-import") (part "passives_20904581_CAPACITOR0201_CAP"))
    )
    (comp (ref "C73")
      (value "2.2uF")
      (footprint "eagle-import:0201_CAP")
      (fields (field (name "MANUFACTURER") "Murata") (field (name "MPN") "GRM033R61A225KE47D"))
      (libsource (lib "eagle-import") (part "passives_20904581_CAPACITOR0201_CAP"))
    )
    (comp (ref "C74")
      (value "2.2uF")
      (footprint "eagle-import:0201_CAP")
      (fields (field (name "MANUFACTURER") "Murata") (field (name "MPN") "GRM033R61A225KE47D"))
      (libsource (lib "eagle-import") (part "passives_20904581_CAPACITOR0201_CAP"))
    )
    (comp (ref "C75")
      (value "2.2uF")
      (footprint "eagle-import:0201_CAP")
      (fields (field (name "MANUFACTURER") "Murata") (field (name "MPN") "GRM033R61A225KE47D"))
      (libsource (lib "eagle-import") (part "passives_20904581_CAPACITOR0201_CAP"))
    )
    (comp (ref "C76")
      (value "4700pF")
      (footprint "eagle-import:CAPC1005X60")
      (fields (field (name "MPN") "KGM05AR71E472KH"))
      (libsource (lib "eagle-import") (part "CCHIP-0402(1005-METRIC)_"))
    )
    (comp (ref "C79")
      (value "1uF")
      (footprint "eagle-import:0201_CAP")
      (fields (field (name "MANUFACTURER") "MURATA") (field (name "MPN") "GRM033R61A105ME44D"))
      (libsource (lib "eagle-import") (part "passives_20904581_CAPACITOR0201_CAP"))
    )
    (comp (ref "C80")
      (value "6pF")
      (footprint "eagle-import:CAPC1005X60")
      (fields (field (name "MANUFACTURER") "Murata") (field (name "MPN") "GCM1555C1H6R0BA16D"))
      (libsource (lib "eagle-import") (part "CCHIP-0402(1005-METRIC)_"))
    )
    (comp (ref "C81")
      (value "6pF")
      (footprint "eagle-import:CAPC1005X60")
      (fields (field (name "MANUFACTURER") "Murata") (field (name "MPN") "GCM1555C1H6R0BA16D"))
      (libsource (lib "eagle-import") (part "CCHIP-0402(1005-METRIC)_"))
    )
    (comp (ref "C93")
      (value "1uF")
      (footprint "eagle-import:0201_CAP")
      (fields (field (name "MANUFACTURER") "Murata") (field (name "MPN") "GRM033R61A105ME44D"))
      (libsource (lib "eagle-import") (part "passives_20904581_CAPACITOR0201_CAP"))
    )
    (comp (ref "CX3")
      (value "DNP")
      (footprint "eagle-import:CAPC1005X60")
      (libsource (lib "eagle-import") (part "CCHIP-0402(1005-METRIC)_"))
    )
    (comp (ref "CX4")
      (value "DNP")
      (footprint "eagle-import:CAPC1005X60")
      (libsource (lib "eagle-import") (part "CCHIP-0402(1005-METRIC)_"))
    )
    (comp (ref "CX5")
      (value "DNP")
      (footprint "eagle-import:CAPC1005X60")
      (libsource (lib "eagle-import") (part "CCHIP-0402(1005-METRIC)_"))
    )
    (comp (ref "D3")
      (value "ZENER")
      (footprint "eagle-import:SODFL1608X70")
      (description "DIODE TVS 5.5V STANDOFF 8V BREAKDOWN SC79")
      (fields (field (name "MANUFACTURER") "NXP SEMICONDUCTOR") (field (name "MPN") "PESD5V0X1UB,135"))
      (libsource (lib "eagle-import") (part "ZENERSODFL(1608-METRIC)_"))
    )
    (comp (ref "L5")
      (value "2.2µH")
      (footprint "eagle-import:0805_CAP")
      (fields (field (name "MANUFACTURER") "Murata") (field (name "MPN") "DFE201210U-2R2M=P2"))
      (libsource (lib "eagle-import") (part "INDUCTOR0805"))
    )
    (comp (ref "L6")
      (value "1.0µH")
      (footprint "eagle-import:0603_CAP")
      (fields (field (name "MANUFACTURER") "Murata") (field (name "MPN") "DFE18SAN1R0ME0L"))
      (libsource (lib "eagle-import") (part "INDUCTOR0603"))
    )
    (comp (ref "L7")
      (value "2.0nH")
      (footprint "eagle-import:INDC1006X60N")
      (description "FIXED IND 2.0NH0.1NH SMD")
      (fields
        (field (name "MANUFACTURER") "Murata")
        (field (name "MPN") "LQG15HS2N0B02D")
        (field (name "TOLERANCE") "+/- 0.1 nH")
      )
      (libsource (lib "eagle-import") (part "LCHIP-0402(1006-METRIC)_"))
    )
    (comp (ref "L8")
      (value "2.2nH")
      (footprint "eagle-import:INDC1006X60N")
      (description "FIXED IND 2.2NH0.1NH SMD")
      (fields
        (field (name "MANUFACTURER") "Murata")
        (field (name "MPN") "LQG15HN2N2B02D")
        (field (name "TOLERANCE") "+/- 0.1 nH")
      )
      (libsource (lib "eagle-import") (part "LCHIP-0402(1006-METRIC)_"))
    )
    (comp (ref "RZ9")
      (value "0")
      (footprint "eagle-import:0402_RES")
      (fields (field (name "MPN") "RMCF0402ZT0R00"))
      (libsource (lib "eagle-import") (part "passives_20904581_RESISTOR0402_RES"))
    )
    (comp (ref "TP8")
      (value "VDDBH")
      (footprint "eagle-import:PAD.03X.03")
      (libsource (lib "eagle-import") (part "TEST-POINT"))
    )
    (comp (ref "TP9")
      (value "VDDP")
      (footprint "eagle-import:PAD.03X.03")
      (libsource (lib "eagle-import") (part "TEST-POINT"))
    )
    (comp (ref "TP10")
      (value "VDDF")
      (footprint "eagle-import:PAD.03X.03")
      (libsource (lib "eagle-import") (part "TEST-POINT"))
    )
    (comp (ref "U1")
      (value "APOLLO4_BLUE_PLUS_SOC_KBR")
      (footprint "eagle-import:APOLLO4_BLUE_SOC_BGA")
      (fields (field (name "MANUFACTURER") "Ambiq") (field (name "MPN") "AMA4B2KP-KBR"))
      (libsource (lib "eagle-import") (part "APOLLO4_BLUE_PLUS_SOC_KBR"))
    )
    (comp (ref "X1")
      (value "ABM12W")
      (footprint "eagle-import:ABM12W")
      (fields
        (field (name "C-LOAD") "6pF")
        (field (name "FREQUENCY") "32 MHz")
        (field (name "MANUFACTURER") "Abracon")
        (field (name "MAX-ESR") "80Ω")
        (field (name "MPN") "ABM12W-32.0000MHZ-6-D1X-T3")
      )
      (libsource (lib "eagle-import") (part "ABM12W"))
    )
    (comp (ref "X3")
      (value "TXC-9HT12")
      (footprint "eagle-import:TXC-9HT12")
      (fields
        (field (name "C-LOAD") "7pF")
        (field (name "FREQUENCY") "32.768 kHz")
        (field (name "MANUFACTURER") "TXC Corp")
        (field (name "MPN") "9HT12-32.768KDZY-T")
      )
      (libsource (lib "eagle-import") (part "TXC-9HT12"))
    )
    (comp (ref "C77")
      (value "1uF")
      (footprint "eagle-import:0201_CAP")
      (fields (field (name "MANUFACTURER") "Murata") (field (name "MPN") "GRM033R61A105ME44D"))
      (libsource (lib "eagle-import") (part "passives_20904581_CAPACITOR0201_CAP"))
    )
    (comp (ref "C78")
      (value "1uF")
      (footprint "eagle-import:0201_CAP")
      (fields (field (name "MANUFACTURER") "Murata") (field (name "MPN") "GRM033R61A105ME44D"))
      (libsource (lib "eagle-import") (part "passives_20904581_CAPACITOR0201_CAP"))
    )
    (comp (ref "D1")
      (value "BICOLOR-SMD")
      (footprint "eagle-import:LED-0606")
      (fields (field (name "MPN") "MCL0606FRD1GR1T"))
      (libsource (lib "eagle-import") (part "BICOLOR-SMD"))
    )
    (comp (ref "D2")
      (value "BICOLOR-SMD")
      (footprint "eagle-import:LED-0606")
      (fields (field (name "MPN") "MCL0606FYW1RD1T"))
      (libsource (lib "eagle-import") (part "BICOLOR-SMD"))
    )
    (comp (ref "J1")
      (value "TC2030-JLINK-NL-2SIDE")
      (footprint "eagle-import:TC2030-IDC-NL-2SIDE")
      (libsource (lib "eagle-import") (part "TC2030-JLINK-NL-2SIDE"))
    )
    (comp (ref "J2")
      (value "TC2030-JLINK-NL-2SIDE")
      (footprint "eagle-import:TC2030-IDC-NL-2SIDE")
      (libsource (lib "eagle-import") (part "TC2030-JLINK-NL-2SIDE"))
    )
    (comp (ref "R2")
      (value "5.1")
      (footprint "eagle-import:0402_RES")
      (fields (field (name "MPN") "RC0402JR-075R1L"))
      (libsource (lib "eagle-import") (part "RESISTOR0402_RES"))
    )
    (comp (ref "R3")
      (value "5.1")
      (footprint "eagle-import:0402_RES")
      (fields (field (name "MPN") "RC0402JR-075R1L"))
      (libsource (lib "eagle-import") (part "RESISTOR0402_RES"))
    )
    (comp (ref "R4")
      (value "15")
      (footprint "eagle-import:0402_RES")
      (fields (field (name "MPN") "RC0402JR-0715RL"))
      (libsource (lib "eagle-import") (part "RESISTOR0402_RES"))
    )
    (comp (ref "R5")
      (value "15")
      (footprint "eagle-import:0402_RES")
      (fields (field (name "MPN") "RC0402JR-0715RL"))
      (libsource (lib "eagle-import") (part "RESISTOR0402_RES"))
    )
    (comp (ref "RZ6")
      (value "0")
      (footprint "eagle-import:0402_RES")
      (fields (field (name "MPN") "RMCF0402ZT0R00"))
      (libsource (lib "eagle-import") (part "passives_20904581_RESISTOR0402_RES"))
    )
    (comp (ref "RZ7")
      (value "0")
      (footprint "eagle-import:0402_RES")
      (fields (field (name "MPN") "RMCF0402ZT0R00"))
      (libsource (lib "eagle-import") (part "passives_20904581_RESISTOR0402_RES"))
    )
    (comp (ref "RZ8")
      (value "0")
      (footprint "eagle-import:0402_RES")
      (fields (field (name "MPN") "RMCF0402ZT0R00"))
      (libsource (lib "eagle-import") (part "passives_20904581_RESISTOR0402_RES"))
    )
    (comp (ref "RZ10")
      (value "0")
      (footprint "eagle-import:0402_RES")
      (fields (field (name "MPN") "RMCF0402ZT0R00"))
      (libsource (lib "eagle-import") (part "passives_20904581_RESISTOR0402_RES"))
    )
    (comp (ref "RZ11")
      (value "0")
      (footprint "eagle-import:0402_RES")
      (fields (field (name "MPN") "RMCF0402ZT0R00"))
      (libsource (lib "eagle-import") (part "passives_20904581_RESISTOR0402_RES"))
    )
    (comp (ref "SJ1")
      (value "JUMPER-SMT_2_NC_TRACE_SILK")
      (footprint "eagle-import:SMT-JUMPER_2_NC_TRACE_SILK")
      (libsource (lib "eagle-import") (part "JUMPER-SMT_2_NC_TRACE_SILK"))
    )
    (comp (ref "VR2")
      (value "TPS7A0218PDQNR")
      (footprint "eagle-import:4-XDFN-EP")
      (libsource (lib "eagle-import") (part "TPS7A0218PDQNR"))
    )
  )
  (nets
    (net (code "1") (name "+1V8") (class "Default")
      (node (ref "C26") (pin "1") (pinfunction "1_1") (pintype "bidirectional"))
      (node (ref "C31") (pin "1") (pinfunction "1_1") (pintype "bidirectional"))
      (node (ref "C35") (pin "1") (pinfunction "1_1") (pintype "bidirectional"))
      (node (ref "C46") (pin "1") (pinfunction "1_1") (pintype "bidirectional"))
      (node (ref "C50") (pin "2") (pinfunction "2_2") (pintype "bidirectional"))
      (node (ref "C62") (pin "P$1") (pinfunction "1_P$1") (pintype "bidirectional"))
      (node (ref "C63") (pin "P$1") (pinfunction "1_P$1") (pintype "bidirectional"))
      (node (ref "C64") (pin "P$1") (pinfunction "1_P$1") (pintype "bidirectional"))
      (node (ref "C65") (pin "P$1") (pinfunction "1_P$1") (pintype "bidirectional"))
      (node (ref "C66") (pin "P$1") (pinfunction "1_P$1") (pintype "bidirectional"))
      (node (ref "C67") (pin "P$1") (pinfunction "1_P$1") (pintype "bidirectional"))
      (node (ref "C75") (pin "P$2") (pinfunction "2_P$2") (pintype "bidirectional"))
      (node (ref "C8") (pin "P$2") (pinfunction "2_P$2") (pintype "bidirectional"))
      (node (ref "J1") (pin "1") (pinfunction "VTREF_1") (pintype "bidirectional"))
      (node (ref "J1") (pin "B1") (pinfunction "VTREF_B1") (pintype "bidirectional"))
      (node (ref "J6") (pin "1") (pinfunction "1_1") (pintype "passive"))
      (node (ref "L2") (pin "P$1") (pinfunction "1_P$1") (pintype "bidirectional"))
      (node (ref "R12") (pin "2") (pinfunction "2_2") (pintype "passive"))
      (node (ref "R16") (pin "2") (pinfunction "2_2") (pintype "passive"))
      (node (ref "R20") (pin "2") (pinfunction "2_2") (pintype "passive"))
      (node (ref "R29") (pin "1") (pinfunction "1_1") (pintype "passive"))
      (node (ref "RX2") (pin "2") (pinfunction "2_2") (pintype "passive"))
      (node (ref "RX5") (pin "1") (pinfunction "1_1") (pintype "passive"))
      (node (ref "RX6") (pin "1") (pinfunction "1_1") (pintype "passive"))
      (node (ref "RX8") (pin "2") (pinfunction "2_2") (pintype "passive"))
      (node (ref "S3") (pin "4") (pinfunction "IN_4") (pintype "bidirectional"))
      (node (ref "SJ1") (pin "2") (pinfunction "2_2") (pintype "passive"))
      (node (ref "SJ4") (pin "1") (pinfunction "1_1") (pintype "passive"))
      (node (ref "SJ7") (pin "3") (pinfunction "3_3") (pintype "passive"))
      (node (ref "TP9") (pin "P$1") (pinfunction "TESTPOINT_P$1") (pintype "bidirectional"))
      (node (ref "U1") (pin "B1") (pinfunction "VDDP-IO_PAD_SUP_B1") (pintype "bidirectional"))
      (node (ref "U1") (pin "C4") (pinfunction "VDDA-ANALOG_SUP_C4") (pintype "bidirectional"))
      (node (ref "U1") (pin "E11") (pinfunction "VDDAUDD_E11") (pintype "bidirectional"))
      (node (ref "U1") (pin "G1") (pinfunction "VDDB-BLE_SUPPLY_G1") (pintype "bidirectional"))
      (node (ref "U1") (pin "M10") (pinfunction "VDDH-HV_SUP_M10") (pintype "bidirectional"))
      (node (ref "U1") (pin "M9") (pinfunction "VDDH2-HV_SUP_M9") (pintype "bidirectional"))
      (node (ref "U2") (pin "B13") (pinfunction "VDD1_B13") (pintype "bidirectional"))
      (node (ref "U6") (pin "28") (pinfunction "VDDIO_28") (pintype "input"))
      (node (ref "U8") (pin "8") (pinfunction "VCC_8") (pintype "bidirectional"))
    )
    (net (code "2") (name "+2V5") (class "Default")
      (node (ref "C32") (pin "1") (pinfunction "1_1") (pintype "bidirectional"))
      (node (ref "C34") (pin "1") (pinfunction "1_1") (pintype "bidirectional"))
      (node (ref "C44") (pin "1") (pinfunction "1_1") (pintype "bidirectional"))
      (node (ref "C47") (pin "2") (pinfunction "2_2") (pintype "bidirectional"))
      (node (ref "C49") (pin "1") (pinfunction "1_1") (pintype "bidirectional"))
      (node (ref "C7") (pin "P$1") (pinfunction "1_P$1") (pintype "bidirectional"))
      (node (ref "C77") (pin "P$1") (pinfunction "1_P$1") (pintype "bidirectional"))
      (node (ref "C90") (pin "P$1") (pinfunction "1_P$1") (pintype "bidirectional"))
      (node (ref "D4") (pin "CATHODE") (pinfunction "CATHODE_CATHODE") (pintype "bidirectional"))
      (node (ref "J5") (pin "1") (pinfunction "1_1") (pintype "passive"))
      (node (ref "L1") (pin "P$2") (pinfunction "2_P$2") (pintype "bidirectional"))
      (node (ref "LS1") (pin "+") (pinfunction "P_+") (pintype "passive"))
      (node (ref "R28") (pin "2") (pinfunction "2_2") (pintype "passive"))
      (node (ref "RX1") (pin "1") (pinfunction "1_1") (pintype "passive"))
      (node (ref "RZ10") (pin "1") (pinfunction "1_1") (pintype "passive"))
      (node (ref "S2") (pin "6") (pinfunction "VDD_6") (pintype "power_in"))
      (node (ref "S3") (pin "1") (pinfunction "IN_1") (pintype "bidirectional"))
      (node (ref "U6") (pin "3") (pinfunction "VDD_3") (pintype "input"))
      (node (ref "VR2") (pin "4") (pinfunction "IN_4") (pintype "bidirectional"))
      (node (ref "VR3") (pin "4") (pinfunction "IN_4") (pintype "bidirectional"))
    )
    (net (code "3") (name "9DOF_H_SDA{slash}H_MISO{slash}TX") (class "Default")
      (node (ref "RX5") (pin "2") (pinfunction "2_2") (pintype "passive"))
      (node (ref "SJ5") (pin "1") (pinfunction "1_1") (pintype "passive"))
      (node (ref "SJ6") (pin "2") (pinfunction "2_2") (pintype "passive"))
      (node (ref "U6") (pin "20") (pinfunction "H_SDA/H_MISO/TX_20") (pintype "bidirectional"))
    )
    (net (code "4") (name "9DOF_SA0{slash}H_MOSI") (class "Default")
      (node (ref "SJ5") (pin "2") (pinfunction "2_2") (pintype "passive"))
      (node (ref "SJ6") (pin "1") (pinfunction "1_1") (pintype "passive"))
      (node (ref "U6") (pin "17") (pinfunction "SA0/H_MOSI_17") (pintype "input"))
    )
    (net (code "5") (name "AGND") (class "Default")
      (node (ref "C1") (pin "2") (pinfunction "2_2") (pintype "passive"))
      (node (ref "C93") (pin "P$2") (pinfunction "2_P$2") (pintype "bidirectional"))
      (node (ref "CX5") (pin "2") (pinfunction "2_2") (pintype "passive"))
      (node (ref "U1") (pin "M1") (pinfunction "RFIOM_M1") (pintype "bidirectional"))
      (node (ref "U1") (pin "M3") (pinfunction "RFSUB-RF_SUBSTRATE_GND_M3") (pintype "bidirectional"))
    )
    (net (code "6") (name "ANT1") (class "Default")
      (node (ref "A1") (pin "FEED") (pinfunction "ANTENNA_FEED") (pintype "bidirectional"))
      (node (ref "U7") (pin "2") (pinfunction "LNA_IN_2") (pintype "bidirectional"))
    )
    (net (code "7") (name "AP4_GP06{slash}TT_FLASH_~{HOLD_IO3}") (class "Default")
      (node (ref "U1") (pin "J5") (pinfunction "GPIO6_J5") (pintype "bidirectional"))
      (node (ref "U8") (pin "7") (pinfunction "~{HOLD}/SIO3_7") (pintype "bidirectional"))
    )
    (net (code "8") (name "AP4_GP08{slash}TT_9DOF_H_SCL{slash}SCK{slash}RX") (class "Default")
      (node (ref "RX6") (pin "2") (pinfunction "2_2") (pintype "passive"))
      (node (ref "U1") (pin "H2") (pinfunction "GPIO31_H2") (pintype "bidirectional"))
      (node (ref "U6") (pin "19") (pinfunction "H_SCL/SCK/RX_19") (pintype "bidirectional"))
    )
    (net (code "9") (name "AP4_GP09{slash}TT_9DOF_H_MOSI") (class "Default")
      (node (ref "SJ5") (pin "3") (pinfunction "3_3") (pintype "passive"))
      (node (ref "U1") (pin "G2") (pinfunction "GPIO32_G2") (pintype "bidirectional"))
    )
    (net (code "10") (name "AP4_GP10{slash}TT_9DOF_H_MISO") (class "Default")
      (node (ref "SJ6") (pin "3") (pinfunction "3_3") (pintype "passive"))
      (node (ref "U1") (pin "G3") (pinfunction "GPIO33_G3") (pintype "bidirectional"))
    )
    (net (code "11") (name "AP4_GP13{slash}TT_9DOF_~{BOOT}") (class "Default")
      (node (ref "R20") (pin "1") (pinfunction "1_1") (pintype "passive"))
      (node (ref "U1") (pin "D5") (pinfunction "GPIO13_D5") (pintype "bidirectional"))
      (node (ref "U6") (pin "4") (pinfunction "~{BOOT}_4") (pintype "input"))
    )
    (net (code "12") (name "AP4_GP14{slash}TT_~{DW_SPI_CS}") (class "Default")
      (node (ref "U1") (pin "D6") (pinfunction "GPIO14_D6") (pintype "bidirectional"))
      (node (ref "U2") (pin "B5") (pinfunction "~{SPICS}_B5") (pintype "bidirectional"))
    )
    (net (code "13") (name "AP4_GP17{slash}TT_9DOF_H_~{INT}") (class "Default")
      (node (ref "U1") (pin "D4") (pinfunction "GPIO17_D4") (pintype "bidirectional"))
      (node (ref "U6") (pin "14") (pinfunction "H_INTN_14") (pintype "output"))
    )
    (net (code "14") (name "AP4_GP18{slash}TT_BATIN") (class "Default")
      (node (ref "C27") (pin "1") (pinfunction "1_1") (pintype "bidirectional"))
      (node (ref "R30") (pin "2") (pinfunction "2_2") (pintype "passive"))
      (node (ref "R31") (pin "1") (pinfunction "1_1") (pintype "passive"))
      (node (ref "U1") (pin "D3") (pinfunction "GPIO18_D3") (pintype "bidirectional"))
    )
    (net (code "15") (name "AP4_GP24{slash}TT_RFSW_V1") (class "Default")
      (node (ref "CX2") (pin "1") (pinfunction "1_1") (pintype "bidirectional"))
      (node (ref "S2") (pin "4") (pinfunction "V1_4") (pintype "input"))
      (node (ref "U1") (pin "E2") (pinfunction "GPIO24_E2") (pintype "bidirectional"))
    )
    (net (code "16") (name "AP4_GP25{slash}TT_RFSW_V2") (class "Default")
      (node (ref "CX1") (pin "1") (pinfunction "1_1") (pintype "bidirectional"))
      (node (ref "S2") (pin "5") (pinfunction "V2_5") (pintype "input"))
      (node (ref "U1") (pin "K5") (pinfunction "GPIO25_K5") (pintype "bidirectional"))
    )
    (net (code "17") (name "AP4_GP26{slash}TT_DW_WAKEUP") (class "Default")
      (node (ref "U1") (pin "L5") (pinfunction "GPIO26_L5") (pintype "bidirectional"))
      (node (ref "U2") (pin "B9") (pinfunction "WAKEUP_B9") (pintype "bidirectional"))
    )
    (net (code "18") (name "AP4_GP27{slash}TT_DW_IRQ") (class "Default")
      (node (ref "R24") (pin "2") (pinfunction "2_2") (pintype "passive"))
      (node (ref "U1") (pin "M5") (pinfunction "GPIO27_M5") (pintype "bidirectional"))
      (node (ref "U2") (pin "B1") (pinfunction "IRQ/GPIO8_B1") (pintype "bidirectional"))
    )
    (net (code "19") (name "AP4_GP30{slash}TT_FLASH_~{WP}") (class "Default")
      (node (ref "U1") (pin "G4") (pinfunction "GPIO30_G4") (pintype "bidirectional"))
      (node (ref "U8") (pin "3") (pinfunction "~{WP}/SIO2_3") (pintype "bidirectional"))
    )
    (net (code "20") (name "AP4_GP31{slash}TT_DW_SPI_CLK") (class "Default")
      (node (ref "U1") (pin "E8") (pinfunction "GPIO8_E8") (pintype "bidirectional"))
      (node (ref "U2") (pin "A8") (pinfunction "SPICLK_A8") (pintype "bidirectional"))
    )
    (net (code "21") (name "AP4_GP32{slash}TT_DW_SPI_IO0") (class "Default")
      (node (ref "U1") (pin "E7") (pinfunction "GPIO9_E7") (pintype "bidirectional"))
      (node (ref "U2") (pin "B7") (pinfunction "SPICDI(MOSI)_B7") (pintype "bidirectional"))
    )
    (net (code "22") (name "AP4_GP33{slash}TT_DW_SPI_IO1") (class "Default")
      (node (ref "U1") (pin "E6") (pinfunction "GPIO10_E6") (pintype "bidirectional"))
      (node (ref "U2") (pin "A6") (pinfunction "SPICDO(MISO)_A6") (pintype "bidirectional"))
    )
    (net (code "23") (name "AP4_GP47{slash}TT_FLASH_SCK") (class "Default")
      (node (ref "U1") (pin "F1") (pinfunction "GPIO47_F1") (pintype "bidirectional"))
      (node (ref "U8") (pin "6") (pinfunction "SCLK_6") (pintype "input"))
    )
    (net (code "24") (name "AP4_GP48{slash}TT_FLASH_PDI_IO0") (class "Default")
      (node (ref "U1") (pin "E1") (pinfunction "GPIO48_E1") (pintype "bidirectional"))
      (node (ref "U8") (pin "5") (pinfunction "SI/SIO0_5") (pintype "bidirectional"))
    )
    (net (code "25") (name "AP4_GP49{slash}TT_FLASH_PDO_IO1") (class "Default")
      (node (ref "U1") (pin "D1") (pinfunction "GPIO49_D1") (pintype "bidirectional"))
      (node (ref "U8") (pin "2") (pinfunction "SO/SIO1_2") (pintype "bidirectional"))
    )
    (net (code "26") (name "AP4_GP50{slash}TT_~{DW_RESET}") (class "Default")
      (node (ref "U1") (pin "A9") (pinfunction "GPIO50_A9") (pintype "bidirectional"))
      (node (ref "U2") (pin "A10") (pinfunction "~{RST}_A10") (pintype "bidirectional"))
    )
    (net (code "27") (name "AP4_GP51{slash}LED1_GREEN") (class "Default")
      (node (ref "R2") (pin "2") (pinfunction "2_2") (pintype "passive"))
      (node (ref "U1") (pin "B9") (pinfunction "GPIO51_B9") (pintype "bidirectional"))
    )
    (net (code "28") (name "AP4_GP53{slash}LED1_RED") (class "Default")
      (node (ref "R5") (pin "2") (pinfunction "2_2") (pintype "passive"))
      (node (ref "U1") (pin "C9") (pinfunction "GPIO53_C9") (pintype "bidirectional"))
    )
    (net (code "29") (name "AP4_GP55{slash}TT_BUZZER_GATE") (class "Default")
      (node (ref "Q2") (pin "G") (pinfunction "G_G") (pintype "passive"))
      (node (ref "R25") (pin "1") (pinfunction "1_1") (pintype "passive"))
      (node (ref "U1") (pin "D9") (pinfunction "GPIO55_D9") (pintype "bidirectional"))
    )
    (net (code "30") (name "AP4_GP58{slash}TT_~{CHG}") (class "Default")
      (node (ref "U1") (pin "J7") (pinfunction "GPIO58_J7") (pintype "bidirectional"))
      (node (ref "U3") (pin "8") (pinfunction "~{CHG}_8") (pintype "bidirectional"))
      (node (ref "U4") (pin "7") (pinfunction "~{CHG}_7") (pintype "bidirectional"))
    )
    (net (code "31") (name "AP4_GP60{slash}TT_~{PG}") (class "Default")
      (node (ref "U1") (pin "K8") (pinfunction "GPIO60_K8") (pintype "bidirectional"))
      (node (ref "U3") (pin "5") (pinfunction "~{PG}_5") (pintype "bidirectional"))
    )
    (net (code "32") (name "AP4_GP63{slash}TT_9DOF_PS0{slash}WAKE") (class "Default")
      (node (ref "U1") (pin "M6") (pinfunction "GPIO63_M6") (pintype "bidirectional"))
      (node (ref "U6") (pin "6") (pinfunction "PS0/WAKE_6") (pintype "input"))
    )
    (net (code "33") (name "AP4_GP65{slash}TT_9DOF_~{RESET}") (class "Default")
      (node (ref "RX8") (pin "1") (pinfunction "1_1") (pintype "passive"))
      (node (ref "U1") (pin "A7") (pinfunction "GPIO65_A7") (pintype "bidirectional"))
      (node (ref "U6") (pin "11") (pinfunction "~{RESET}_11") (pintype "input"))
    )
    (net (code "34") (name "AP4_GP66{slash}TT_QI_TS_CTRL") (class "Default")
      (node (ref "C30") (pin "1") (pinfunction "1_1") (pintype "bidirectional"))
      (node (ref "RT1") (pin "2") (pinfunction "2_2") (pintype "passive"))
      (node (ref "U1") (pin "A8") (pinfunction "GPIO66_A8") (pintype "bidirectional"))
      (node (ref "U4") (pin "13") (pinfunction "TS/CTRL_13") (pintype "bidirectional"))
    )
    (net (code "35") (name "AP4_GP69{slash}TT_FLASH_~{CS}") (class "Default")
      (node (ref "RX2") (pin "1") (pinfunction "1_1") (pintype "passive"))
      (node (ref "U1") (pin "B8") (pinfunction "GPIO69_B8") (pintype "bidirectional"))
      (node (ref "U8") (pin "1") (pinfunction "~{CS}_1") (pintype "input"))
    )
    (net (code "36") (name "AP4_GP72{slash}TT_9DOF_H_~{CS}") (class "Default")
      (node (ref "U1") (pin "C8") (pinfunction "GPIO72_C8") (pintype "bidirectional"))
      (node (ref "U6") (pin "18") (pinfunction "H_~{CS}_18") (pintype "input"))
    )
    (net (code "37") (name "AP4_GP79{slash}LED2_RED") (class "Default")
      (node (ref "R4") (pin "2") (pinfunction "2_2") (pintype "passive"))
      (node (ref "U1") (pin "M11") (pinfunction "GPIO79_M11") (pintype "bidirectional"))
    )
    (net (code "38") (name "AP4_GP80{slash}SWTRACE0") (class "Default")
      (node (ref "J2") (pin "2") (pinfunction "SWDIO_2") (pintype "bidirectional"))
      (node (ref "J2") (pin "B2") (pinfunction "SWDIO_B2") (pintype "bidirectional"))
      (node (ref "U1") (pin "K10") (pinfunction "GPIO80_K10") (pintype "bidirectional"))
    )
    (net (code "39") (name "AP4_GP81{slash}SWTRACE1") (class "Default")
      (node (ref "J2") (pin "4") (pinfunction "SWDCLK_4") (pintype "bidirectional"))
      (node (ref "J2") (pin "B4") (pinfunction "SWDCLK_B4") (pintype "bidirectional"))
      (node (ref "U1") (pin "L10") (pinfunction "GPIO81_L10") (pintype "bidirectional"))
    )
    (net (code "40") (name "AP4_GP82{slash}SWTRACE2") (class "Default")
      (node (ref "J2") (pin "6") (pinfunction "SWO_6") (pintype "bidirectional"))
      (node (ref "J2") (pin "B6") (pinfunction "SWO_B6") (pintype "bidirectional"))
      (node (ref "U1") (pin "L9") (pinfunction "GPIO82_L9") (pintype "bidirectional"))
    )
    (net (code "41") (name "AP4_GP83{slash}SWTRACE3") (class "Default")
      (node (ref "J2") (pin "3") (pinfunction "~{RESET}_3") (pintype "bidirectional"))
      (node (ref "J2") (pin "B3") (pinfunction "~{RESET}_B3") (pintype "bidirectional"))
      (node (ref "U1") (pin "K9") (pinfunction "GPIO83_K9") (pintype "bidirectional"))
    )
    (net (code "42") (name "AP4_GP88{slash}LED2_YLW") (class "Default")
      (node (ref "R3") (pin "2") (pinfunction "2_2") (pintype "passive"))
      (node (ref "U1") (pin "F9") (pinfunction "GPIO88_F9") (pintype "bidirectional"))
    )
    (net (code "43") (name "AP4_SWDCLK") (class "Default")
      (node (ref "J1") (pin "4") (pinfunction "SWDCLK_4") (pintype "bidirectional"))
      (node (ref "J1") (pin "B4") (pinfunction "SWDCLK_B4") (pintype "bidirectional"))
      (node (ref "U1") (pin "K3") (pinfunction "GPIO20_K3") (pintype "bidirectional"))
    )
    (net (code "44") (name "AP4_SWDIO") (class "Default")
      (node (ref "J1") (pin "2") (pinfunction "SWDIO_2") (pintype "bidirectional"))
      (node (ref "J1") (pin "B2") (pinfunction "SWDIO_B2") (pintype "bidirectional"))
      (node (ref "U1") (pin "J3") (pinfunction "GPIO21_J3") (pintype "bidirectional"))
    )
    (net (code "45") (name "AP4_SWO") (class "Default")
      (node (ref "J1") (pin "6") (pinfunction "SWO_6") (pintype "bidirectional"))
      (node (ref "J1") (pin "B6") (pinfunction "SWO_B6") (pintype "bidirectional"))
      (node (ref "U1") (pin "L4") (pinfunction "GPIO3_L4") (pintype "bidirectional"))
    )
    (net (code "46") (name "AP4_SWTRACECLK") (class "Default")
      (node (ref "J2") (pin "1") (pinfunction "VTREF_1") (pintype "bidirectional"))
      (node (ref "J2") (pin "B1") (pinfunction "VTREF_B1") (pintype "bidirectional"))
      (node (ref "U1") (pin "F12") (pinfunction "GPIO38_F12") (pintype "bidirectional"))
    )
    (net (code "47") (name "AP4_USB0_N") (class "Default")
      (node (ref "U1") (pin "M8") (pinfunction "USB0PN_M8") (pintype "bidirectional"))
    )
    (net (code "48") (name "AP4_USB0_P") (class "Default")
      (node (ref "U1") (pin "M7") (pinfunction "USB0PP_M7") (pintype "bidirectional"))
    )
    (net (code "49") (name "AP4_VDDBH") (class "Default")
      (node (ref "C69") (pin "1") (pinfunction "1_1") (pintype "bidirectional"))
      (node (ref "L6") (pin "2") (pinfunction "2_2") (pintype "bidirectional"))
      (node (ref "RZ9") (pin "1") (pinfunction "1_1") (pintype "passive"))
      (node (ref "TP8") (pin "P$1") (pinfunction "TESTPOINT_P$1") (pintype "bidirectional"))
      (node (ref "U1") (pin "G12") (pinfunction "VDDBH--BLE_BUCK_VOUT_G12") (pintype "bidirectional"))
    )
    (net (code "50") (name "AP4_VDDBH_RF") (class "Default")
      (node (ref "C93") (pin "P$1") (pinfunction "1_P$1") (pintype "bidirectional"))
      (node (ref "RZ9") (pin "2") (pinfunction "2_2") (pintype "passive"))
      (node (ref "U1") (pin "J1") (pinfunction "VDDBH_RF--BLE_BUCK_RF_VOUT_J1") (pintype "bidirectional"))
    )
    (net (code "51") (name "AP4_VDDF") (class "Default")
      (node (ref "C61") (pin "P$1") (pinfunction "1_P$1") (pintype "bidirectional"))
      (node (ref "C75") (pin "P$1") (pinfunction "1_P$1") (pintype "bidirectional"))
      (node (ref "TP10") (pin "P$1") (pinfunction "TESTPOINT_P$1") (pintype "bidirectional"))
      (node (ref "U1") (pin "C2") (pinfunction "VDDF-MEM_C2") (pintype "bidirectional"))
    )
    (net (code "52") (name "AP4_VDDMIPI_1P8") (class "Default")
      (node (ref "C70") (pin "P$1") (pinfunction "1_P$1") (pintype "bidirectional"))
      (node (ref "RZ8") (pin "1") (pinfunction "1_1") (pintype "passive"))
      (node (ref "U1") (pin "H10") (pinfunction "VDD18-MIPI_H10") (pintype "bidirectional"))
    )
    (net (code "53") (name "AP4_VDDUSB_0P9") (class "Default")
      (node (ref "C73") (pin "P$1") (pinfunction "1_P$1") (pintype "bidirectional"))
      (node (ref "RZ6") (pin "1") (pinfunction "1_1") (pintype "passive"))
      (node (ref "U1") (pin "L7") (pinfunction "VDDUSB0P9_L7") (pintype "bidirectional"))
    )
    (net (code "54") (name "AP4_VDDUSB_3P3") (class "Default")
      (node (ref "C74") (pin "P$1") (pinfunction "1_P$1") (pintype "bidirectional"))
      (node (ref "RZ7") (pin "1") (pinfunction "1_1") (pintype "passive"))
      (node (ref "U1") (pin "K7") (pinfunction "VDDUSB33_K7") (pintype "bidirectional"))
    )
    (net (code "55") (name "AP4_~{RESET}") (class "Default")
      (node (ref "C76") (pin "1") (pinfunction "1_1") (pintype "passive"))
      (node (ref "D3") (pin "1") (pinfunction "C_1") (pintype "passive"))
      (node (ref "J1") (pin "3") (pinfunction "~{RESET}_3") (pintype "bidirectional"))
      (node (ref "J1") (pin "B3") (pinfunction "~{RESET}_B3") (pintype "bidirectional"))
      (node (ref "U1") (pin "A6") (pinfunction "~{RST}_A6") (pintype "input"))
    )
    (net (code "56") (name "BATT_THERM") (class "Default")
      (node (ref "J4") (pin "2") (pinfunction "2_2") (pintype "bidirectional"))
      (node (ref "J4") (pin "2SUPP") (pinfunction "2_2SUPP") (pintype "bidirectional"))
      (node (ref "SJ2") (pin "3") (pinfunction "3_3") (pintype "passive"))
    )
    (net (code "57") (name "BATT_TS") (class "Default")
      (node (ref "SJ2") (pin "2") (pinfunction "2_2") (pintype "passive"))
      (node (ref "U3") (pin "9") (pinfunction "TS_9") (pintype "bidirectional"))
    )
    (net (code "58") (name "BNO_ENV_SCL") (class "Default")
      (node (ref "R12") (pin "1") (pinfunction "1_1") (pintype "passive"))
      (node (ref "U6") (pin "15") (pinfunction "ENV_SCL_15") (pintype "bidirectional"))
    )
    (net (code "59") (name "BNO_ENV_SDA") (class "Default")
      (node (ref "R16") (pin "1") (pinfunction "1_1") (pintype "passive"))
      (node (ref "U6") (pin "16") (pinfunction "ENV_SDA_16") (pintype "bidirectional"))
    )
    (net (code "60") (name "D+") (class "Default")
      (node (ref "XJ1") (pin "A6") (pinfunction "DP1_A6") (pintype "bidirectional"))
      (node (ref "XJ1") (pin "B6") (pinfunction "DP2_B6") (pintype "bidirectional"))
    )
    (net (code "61") (name "D-") (class "Default")
      (node (ref "XJ1") (pin "A7") (pinfunction "DN1_A7") (pintype "bidirectional"))
      (node (ref "XJ1") (pin "B7") (pinfunction "DN2_B7") (pintype "bidirectional"))
    )
    (net (code "62") (name "DW_EXTON") (class "Default")
      (node (ref "RX1") (pin "2") (pinfunction "2_2") (pintype "passive"))
      (node (ref "S3") (pin "2") (pinfunction "CTL_2") (pintype "bidirectional"))
      (node (ref "S3") (pin "3") (pinfunction "CTL_3") (pintype "bidirectional"))
      (node (ref "SJ4") (pin "2") (pinfunction "2_2") (pintype "passive"))
      (node (ref "VR3") (pin "3") (pinfunction "EN_3") (pintype "input"))
    )
    (net (code "63") (name "DW_EXTON_RAW") (class "Default")
      (node (ref "SJ4") (pin "3") (pinfunction "3_3") (pintype "passive"))
      (node (ref "U2") (pin "A12") (pinfunction "EXTON_A12") (pintype "bidirectional"))
    )
    (net (code "64") (name "DW_GPIO6{slash}EXTRXE") (class "Default")
      (node (ref "SJ3") (pin "3") (pinfunction "3_3") (pintype "passive"))
      (node (ref "TP6") (pin "P$1") (pinfunction "TESTPOINT_P$1") (pintype "bidirectional"))
      (node (ref "U2") (pin "C4") (pinfunction "GPIO6/EXTRXE/SPIPHA_C4") (pintype "bidirectional"))
    )
    (net (code "65") (name "DW_SYNC") (class "Default")
      (node (ref "TP7") (pin "P$1") (pinfunction "TESTPOINT_P$1") (pintype "bidirectional"))
      (node (ref "U2") (pin "G2") (pinfunction "GPIO7/SYNC_G2") (pintype "bidirectional"))
    )
    (net (code "66") (name "DW_VDD2_SUP") (class "Default")
      (node (ref "C13") (pin "P$1") (pinfunction "P$1_P$1") (pintype "bidirectional"))
      (node (ref "C24") (pin "P$1") (pinfunction "P$1_P$1") (pintype "bidirectional"))
      (node (ref "C55") (pin "P$1") (pinfunction "P$1_P$1") (pintype "bidirectional"))
      (node (ref "FB1") (pin "P$1") (pinfunction "P$1_P$1") (pintype "bidirectional"))
      (node (ref "RZ1") (pin "2") (pinfunction "2_2") (pintype "passive"))
      (node (ref "U2") (pin "B15") (pinfunction "VDD2B_B15") (pintype "bidirectional"))
    )
    (net (code "67") (name "DW_VDD3_SUP") (class "Default")
      (node (ref "C14") (pin "P$2") (pinfunction "P$2_P$2") (pintype "bidirectional"))
      (node (ref "C22") (pin "P$2") (pinfunction "P$2_P$2") (pintype "bidirectional"))
      (node (ref "C54") (pin "P$2") (pinfunction "P$2_P$2") (pintype "bidirectional"))
      (node (ref "RZ2") (pin "2") (pinfunction "2_2") (pintype "passive"))
      (node (ref "U2") (pin "D15") (pinfunction "VDD3_D15") (pintype "bidirectional"))
    )
    (net (code "68") (name "GND") (class "Default")
      (node (ref "C11") (pin "P$2") (pinfunction "P$2_P$2") (pintype "bidirectional"))
      (node (ref "C12") (pin "P$2") (pinfunction "P$2_P$2") (pintype "bidirectional"))
      (node (ref "C13") (pin "P$2") (pinfunction "P$2_P$2") (pintype "bidirectional"))
      (node (ref "C14") (pin "P$1") (pinfunction "P$1_P$1") (pintype "bidirectional"))
      (node (ref "C22") (pin "P$1") (pinfunction "P$1_P$1") (pintype "bidirectional"))
      (node (ref "C23") (pin "2") (pinfunction "2_2") (pintype "bidirectional"))
      (node (ref "C24") (pin "P$2") (pinfunction "P$2_P$2") (pintype "bidirectional"))
      (node (ref "C25") (pin "2") (pinfunction "2_2") (pintype "bidirectional"))
      (node (ref "C26") (pin "2") (pinfunction "2_2") (pintype "bidirectional"))
      (node (ref "C27") (pin "2") (pinfunction "2_2") (pintype "bidirectional"))
      (node (ref "C28") (pin "2") (pinfunction "2_2") (pintype "bidirectional"))
      (node (ref "C29") (pin "2") (pinfunction "2_2") (pintype "bidirectional"))
      (node (ref "C3") (pin "P$2") (pinfunction "P$2_P$2") (pintype "bidirectional"))
      (node (ref "C30") (pin "2") (pinfunction "2_2") (pintype "bidirectional"))
      (node (ref "C31") (pin "2") (pinfunction "2_2") (pintype "bidirectional"))
      (node (ref "C32") (pin "2") (pinfunction "2_2") (pintype "bidirectional"))
      (node (ref "C33") (pin "2") (pinfunction "2_2") (pintype "bidirectional"))
      (node (ref "C34") (pin "2") (pinfunction "2_2") (pintype "bidirectional"))
      (node (ref "C35") (pin "2") (pinfunction "2_2") (pintype "bidirectional"))
      (node (ref "C36") (pin "2") (pinfunction "2_2") (pintype "bidirectional"))
      (node (ref "C37") (pin "P$1") (pinfunction "P$1_P$1") (pintype "bidirectional"))
      (node (ref "C4") (pin "P$2") (pinfunction "P$2_P$2") (pintype "bidirectional"))
      (node (ref "C40") (pin "1") (pinfunction "1_1") (pintype "bidirectional"))
      (node (ref "C41") (pin "2") (pinfunction "2_2") (pintype "bidirectional"))
      (node (ref "C42") (pin "2") (pinfunction "2_2") (pintype "bidirectional"))
      (node (ref "C43") (pin "P$2") (pinfunction "P$2_P$2") (pintype "bidirectional"))
      (node (ref "C44") (pin "2") (pinfunction "2_2") (pintype "bidirectional"))
      (node (ref "C45") (pin "1") (pinfunction "1_1") (pintype "bidirectional"))
      (node (ref "C46") (pin "2") (pinfunction "2_2") (pintype "bidirectional"))
      (node (ref "C47") (pin "1") (pinfunction "1_1") (pintype "bidirectional"))
      (node (ref "C48") (pin "2") (pinfunction "2_2") (pintype "bidirectional"))
      (node (ref "C49") (pin "2") (pinfunction "2_2") (pintype "bidirectional"))
      (node (ref "C5") (pin "P$1") (pinfunction "1_P$1") (pintype "bidirectional"))
      (node (ref "C50") (pin "1") (pinfunction "1_1") (pintype "bidirectional"))
      (node (ref "C53") (pin "2") (pinfunction "2_2") (pintype "bidirectional"))
      (node (ref "C54") (pin "P$1") (pinfunction "P$1_P$1") (pintype "bidirectional"))
      (node (ref "C55") (pin "P$2") (pinfunction "P$2_P$2") (pintype "bidirectional"))
      (node (ref "C56") (pin "2") (pinfunction "2_2") (pintype "bidirectional"))
      (node (ref "C57") (pin "2") (pinfunction "2_2") (pintype "bidirectional"))
      (node (ref "C58") (pin "P$2") (pinfunction "2_P$2") (pintype "bidirectional"))
      (node (ref "C59") (pin "P$2") (pinfunction "2_P$2") (pintype "bidirectional"))
      (node (ref "C6") (pin "P$1") (pinfunction "1_P$1") (pintype "bidirectional"))
      (node (ref "C60") (pin "P$2") (pinfunction "2_P$2") (pintype "bidirectional"))
      (node (ref "C61") (pin "P$2") (pinfunction "2_P$2") (pintype "bidirectional"))
      (node (ref "C62") (pin "P$2") (pinfunction "2_P$2") (pintype "bidirectional"))
      (node (ref "C63") (pin "P$2") (pinfunction "2_P$2") (pintype "bidirectional"))
      (node (ref "C64") (pin "P$2") (pinfunction "2_P$2") (pintype "bidirectional"))
      (node (ref "C65") (pin "P$2") (pinfunction "2_P$2") (pintype "bidirectional"))
      (node (ref "C66") (pin "P$2") (pinfunction "2_P$2") (pintype "bidirectional"))
      (node (ref "C67") (pin "P$2") (pinfunction "2_P$2") (pintype "bidirectional"))
      (node (ref "C69") (pin "2") (pinfunction "2_2") (pintype "bidirectional"))
      (node (ref "C70") (pin "P$2") (pinfunction "2_P$2") (pintype "bidirectional"))
      (node (ref "C71") (pin "P$1") (pinfunction "1_P$1") (pintype "bidirectional"))
      (node (ref "C72") (pin "P$2") (pinfunction "2_P$2") (pintype "bidirectional"))
      (node (ref "C73") (pin "P$2") (pinfunction "2_P$2") (pintype "bidirectional"))
      (node (ref "C74") (pin "P$2") (pinfunction "2_P$2") (pintype "bidirectional"))
      (node (ref "C76") (pin "2") (pinfunction "2_2") (pintype "passive"))
      (node (ref "C77") (pin "P$2") (pinfunction "2_P$2") (pintype "bidirectional"))
      (node (ref "C78") (pin "P$2") (pinfunction "2_P$2") (pintype "bidirectional"))
      (node (ref "C79") (pin "P$1") (pinfunction "1_P$1") (pintype "bidirectional"))
      (node (ref "C80") (pin "2") (pinfunction "2_2") (pintype "passive"))
      (node (ref "C81") (pin "2") (pinfunction "2_2") (pintype "passive"))
      (node (ref "C90") (pin "P$2") (pinfunction "2_P$2") (pintype "bidirectional"))
      (node (ref "C91") (pin "P$2") (pinfunction "2_P$2") (pintype "bidirectional"))
      (node (ref "CX1") (pin "2") (pinfunction "2_2") (pintype "bidirectional"))
      (node (ref "CX2") (pin "2") (pinfunction "2_2") (pintype "bidirectional"))
      (node (ref "CX3") (pin "2") (pinfunction "2_2") (pintype "passive"))
      (node (ref "CX4") (pin "2") (pinfunction "2_2") (pintype "passive"))
      (node (ref "D3") (pin "2") (pinfunction "A_2") (pintype "passive"))
      (node (ref "J1") (pin "5") (pinfunction "GND_5") (pintype "bidirectional"))
      (node (ref "J1") (pin "B5") (pinfunction "GND_B5") (pintype "bidirectional"))
      (node (ref "J2") (pin "5") (pinfunction "GND_5") (pintype "bidirectional"))
      (node (ref "J2") (pin "B5") (pinfunction "GND_B5") (pintype "bidirectional"))
      (node (ref "J3") (pin "2") (pinfunction "2_2") (pintype "passive"))
      (node (ref "J4") (pin "1") (pinfunction "1_1") (pintype "bidirectional"))
      (node (ref "J4") (pin "1SUPP") (pinfunction "1_1SUPP") (pintype "bidirectional"))
      (node (ref "Q2") (pin "S") (pinfunction "S_S") (pintype "passive"))
      (node (ref "R1") (pin "2") (pinfunction "2_2") (pintype "passive"))
      (node (ref "R15") (pin "1") (pinfunction "1_1") (pintype "passive"))
      (node (ref "R24") (pin "1") (pinfunction "1_1") (pintype "passive"))
      (node (ref "R25") (pin "2") (pinfunction "2_2") (pintype "passive"))
      (node (ref "R26") (pin "1") (pinfunction "1_1") (pintype "passive"))
      (node (ref "R27") (pin "1") (pinfunction "1_1") (pintype "passive"))
      (node (ref "R30") (pin "1") (pinfunction "1_1") (pintype "passive"))
      (node (ref "R6") (pin "2") (pinfunction "2_2") (pintype "passive"))
      (node (ref "RX14") (pin "1") (pinfunction "1_1") (pintype "passive"))
      (node (ref "RX7") (pin "1") (pinfunction "1_1") (pintype "passive"))
      (node (ref "RZ6") (pin "2") (pinfunction "2_2") (pintype "passive"))
      (node (ref "RZ7") (pin "2") (pinfunction "2_2") (pintype "passive"))
      (node (ref "RZ8") (pin "2") (pinfunction "2_2") (pintype "passive"))
      (node (ref "S2") (pin "10") (pinfunction "GND_10") (pintype "bidirectional"))
      (node (ref "S2") (pin "12") (pinfunction "GND_12") (pintype "bidirectional"))
      (node (ref "S2") (pin "2") (pinfunction "GND_2") (pintype "bidirectional"))
      (node (ref "S2") (pin "7") (pinfunction "GND_7") (pintype "bidirectional"))
      (node (ref "S2") (pin "8") (pinfunction "GND_8") (pintype "bidirectional"))
      (node (ref "S2") (pin "PAD") (pinfunction "GND_PAD") (pintype "bidirectional"))
      (node (ref "S3") (pin "6") (pinfunction "GND_6") (pintype "bidirectional"))
      (node (ref "S3") (pin "7") (pinfunction "GND_7") (pintype "bidirectional"))
      (node (ref "S3") (pin "PAD") (pinfunction "GND_PAD") (pintype "bidirectional"))
      (node (ref "S4") (pin "G1") (pinfunction "GND_G1") (pintype "bidirectional"))
      (node (ref "S4") (pin "G2") (pinfunction "GND_G2") (pintype "bidirectional"))
      (node (ref "SJ3") (pin "1") (pinfunction "1_1") (pintype "passive"))
      (node (ref "SJ7") (pin "1") (pinfunction "1_1") (pintype "passive"))
      (node (ref "U1") (pin "B12") (pinfunction "VSSAUDA_B12") (pintype "bidirectional"))
      (node (ref "U1") (pin "B2") (pinfunction "VSSP-BUCK_REGS_GND_B2") (pintype "bidirectional"))
      (node (ref "U1") (pin "B5") (pinfunction "VSSA-ANALOG_GND_B5") (pintype "bidirectional"))
      (node (ref "U1") (pin "D2") (pinfunction "VSS-DGND_FOR_VDDF_AND_PADS_D2") (pintype "bidirectional"))
      (node (ref "U1") (pin "E12") (pinfunction "VSSAUDD_E12") (pintype "bidirectional"))
      (node (ref "U1") (pin "H1") (pinfunction "VSSB-BLE_UNREG_GND_H1") (pintype "bidirectional"))
      (node (ref "U1") (pin "J10") (pinfunction "VSS18-MIPI_J10") (pintype "bidirectional"))
      (node (ref "U1") (pin "L1") (pinfunction "VSSVCO-BLECORE_GND_FOR_VCO_L1") (pintype "bidirectional"))
      (node (ref "U1") (pin "L2") (pinfunction "VSSS-HVSIMOBUCK_GND_L2") (pintype "bidirectional"))
      (node (ref "U1") (pin "L8") (pinfunction "VSSAUSB_L8") (pintype "bidirectional"))
      (node (ref "U2") (pin "A14") (pinfunction "VSS1_A14") (pintype "bidirectional"))
      (node (ref "U2") (pin "A2") (pinfunction "VSS_A2") (pintype "bidirectional"))
      (node (ref "U2") (pin "B11") (pinfunction "VSS1_B11") (pintype "bidirectional"))
      (node (ref "U2") (pin "B3") (pinfunction "VSS_B3") (pintype "bidirectional"))
      (node (ref "U2") (pin "C10") (pinfunction "VSS1_C10") (pintype "bidirectional"))
      (node (ref "U2") (pin "C12") (pinfunction "VSS3_C12") (pintype "bidirectional"))
      (node (ref "U2") (pin "C6") (pinfunction "VSS_C6") (pintype "bidirectional"))
      (node (ref "U2") (pin "C8") (pinfunction "VSS1_C8") (pintype "bidirectional"))
      (node (ref "U2") (pin "D11") (pinfunction "VSS2_D11") (pintype "bidirectional"))
      (node (ref "U2") (pin "D13") (pinfunction "VSS3_D13") (pintype "bidirectional"))
      (node (ref "U2") (pin "D5") (pinfunction "VSS_D5") (pintype "bidirectional"))
      (node (ref "U2") (pin "D7") (pinfunction "VSS_D7") (pintype "bidirectional"))
      (node (ref "U2") (pin "D9") (pinfunction "VSS1_D9") (pintype "bidirectional"))
      (node (ref "U2") (pin "E10") (pinfunction "GND-RF_E10") (pintype "bidirectional"))
      (node (ref "U2") (pin "E12") (pinfunction "GND-RF_E12") (pintype "bidirectional"))
      (node (ref "U2") (pin "E14") (pinfunction "VSS2_E14") (pintype "bidirectional"))
      (node (ref "U2") (pin "E6") (pinfunction "GND-RF_E6") (pintype "bidirectional"))
      (node (ref "U2") (pin "F7") (pinfunction "GND-RF_F7") (pintype "bidirectional"))
      (node (ref "U2") (pin "F9") (pinfunction "GND-RF_F9") (pintype "bidirectional"))
      (node (ref "U2") (pin "G10") (pinfunction "GND-RF_G10") (pintype "bidirectional"))
      (node (ref "U2") (pin "G6") (pinfunction "GND-RF_G6") (pintype "bidirectional"))
      (node (ref "U2") (pin "H1") (pinfunction "GND-RF_H1") (pintype "bidirectional"))
      (node (ref "U2") (pin "H13") (pinfunction "GND-RF_H13") (pintype "bidirectional"))
      (node (ref "U2") (pin "H3") (pinfunction "GND-RF_H3") (pintype "bidirectional"))
      (node (ref "U2") (pin "H7") (pinfunction "GND-RF_H7") (pintype "bidirectional"))
      (node (ref "U2") (pin "H9") (pinfunction "GND-RF_H9") (pintype "bidirectional"))
      (node (ref "U3") (pin "3") (pinfunction "VSS_3") (pintype "bidirectional"))
      (node (ref "U3") (pin "7") (pinfunction "ISET2_7") (pintype "bidirectional"))
      (node (ref "U3") (pin "PAD") (pinfunction "VSS_PAD") (pintype "bidirectional"))
      (node (ref "U4") (pin "1") (pinfunction "PGND_1") (pintype "bidirectional"))
      (node (ref "U4") (pin "10") (pinfunction "EN1_10") (pintype "bidirectional"))
      (node (ref "U4") (pin "11") (pinfunction "EN2_11") (pintype "bidirectional"))
      (node (ref "U4") (pin "20") (pinfunction "PGND_20") (pintype "bidirectional"))
      (node (ref "U4") (pin "PAD") (pinfunction "PGND_PAD") (pintype "bidirectional"))
      (node (ref "U6") (pin "10") (pinfunction "CLKSEL0_10") (pintype "output"))
      (node (ref "U6") (pin "2") (pinfunction "GND_2") (pintype "bidirectional"))
      (node (ref "U6") (pin "25") (pinfunction "GNDIO_25") (pintype "bidirectional"))
      (node (ref "U7") (pin "3") (pinfunction "GND_3") (pintype "bidirectional"))
      (node (ref "U7") (pin "4") (pinfunction "GND_4") (pintype "bidirectional"))
      (node (ref "U7") (pin "5") (pinfunction "GND_5") (pintype "bidirectional"))
      (node (ref "U7") (pin "7") (pinfunction "GND_7") (pintype "bidirectional"))
      (node (ref "U7") (pin "9") (pinfunction "GND_9") (pintype "bidirectional"))
      (node (ref "U8") (pin "4") (pinfunction "GND_4") (pintype "bidirectional"))
      (node (ref "VR1") (pin "13") (pinfunction "GND2_13") (pintype "bidirectional"))
      (node (ref "VR1") (pin "3") (pinfunction "GND2_3") (pintype "bidirectional"))
      (node (ref "VR1") (pin "9") (pinfunction "GND1_9") (pintype "bidirectional"))
      (node (ref "VR2") (pin "2") (pinfunction "GND_2") (pintype "bidirectional"))
      (node (ref "VR2") (pin "PAD") (pinfunction "GND_PAD") (pintype "bidirectional"))
      (node (ref "VR3") (pin "2") (pinfunction "GND_2") (pintype "bidirectional"))
      (node (ref "VR3") (pin "PAD") (pinfunction "GND_PAD") (pintype "bidirectional"))
      (node (ref "X1") (pin "2") (pinfunction "GND_2") (pintype "bidirectional"))
      (node (ref "X1") (pin "4") (pinfunction "GND_4") (pintype "bidirectional"))
      (node (ref "X4") (pin "2") (pinfunction "GND_2") (pintype "bidirectional"))
      (node (ref "X4") (pin "4") (pinfunction "GND_4") (pintype "bidirectional"))
      (node (ref "XJ1") (pin "A1/B12") (pinfunction "GND_A1/B12") (pintype "power_in"))
      (node (ref "XJ1") (pin "B1/A12") (pinfunction "GND_B1/A12") (pintype "power_in"))
      (node (ref "XJ1") (pin "S1") (pinfunction "GND_S1") (pintype "power_in"))
      (node (ref "XJ1") (pin "S2") (pinfunction "GND_S2") (pintype "power_in"))
      (node (ref "XJ1") (pin "S3") (pinfunction "GND_S3") (pintype "power_in"))
      (node (ref "XJ1") (pin "S4") (pinfunction "GND_S4") (pintype "power_in"))
      (node (ref "XR16") (pin "2") (pinfunction "2_2") (pintype "passive"))
      (node (ref "XR17") (pin "2") (pinfunction "2_2") (pintype "passive"))
      (node (ref "XR19") (pin "1") (pinfunction "1_1") (pintype "passive"))
    )
    (net (code "69") (name "Net-(A4-ANTENNA)") (class "Default")
      (node (ref "A4") (pin "S1") (pinfunction "ANTENNA_S1") (pintype "bidirectional"))
      (node (ref "L8") (pin "2") (pinfunction "2_2") (pintype "passive"))
    )
    (net (code "70") (name "Net-(C1-Pad1)") (class "Default")
      (node (ref "C1") (pin "1") (pinfunction "1_1") (pintype "passive"))
      (node (ref "L7") (pin "2") (pinfunction "2_2") (pintype "passive"))
      (node (ref "L8") (pin "1") (pinfunction "1_1") (pintype "passive"))
    )
    (net (code "71") (name "Net-(C2-1)") (class "Default")
      (node (ref "C2") (pin "P$1") (pinfunction "1_P$1") (pintype "bidirectional"))
      (node (ref "U2") (pin "H11") (pinfunction "RF1_H11") (pintype "bidirectional"))
    )
    (net (code "72") (name "Net-(C2-2)") (class "Default")
      (node (ref "C2") (pin "P$2") (pinfunction "2_P$2") (pintype "bidirectional"))
      (node (ref "S2") (pin "11") (pinfunction "RFC_11") (pintype "bidirectional"))
    )
    (net (code "73") (name "Net-(C5-2)") (class "Default")
      (node (ref "C5") (pin "P$2") (pinfunction "2_P$2") (pintype "bidirectional"))
      (node (ref "U6") (pin "27") (pinfunction "XIN32_27") (pintype "bidirectional"))
      (node (ref "X2") (pin "2") (pinfunction "2_2") (pintype "bidirectional"))
    )
    (net (code "74") (name "Net-(C6-2)") (class "Default")
      (node (ref "C6") (pin "P$2") (pinfunction "2_P$2") (pintype "bidirectional"))
      (node (ref "U6") (pin "26") (pinfunction "XOUT32/CLKSEL1_26") (pintype "bidirectional"))
      (node (ref "X2") (pin "1") (pinfunction "1_1") (pintype "bidirectional"))
    )
    (net (code "75") (name "Net-(C7-2)") (class "Default")
      (node (ref "C7") (pin "P$2") (pinfunction "2_P$2") (pintype "bidirectional"))
      (node (ref "R26") (pin "2") (pinfunction "2_2") (pintype "passive"))
      (node (ref "R28") (pin "1") (pinfunction "1_1") (pintype "passive"))
      (node (ref "VR1") (pin "10") (pinfunction "FB2_10") (pintype "bidirectional"))
    )
    (net (code "76") (name "Net-(C8-1)") (class "Default")
      (node (ref "C8") (pin "P$1") (pinfunction "1_P$1") (pintype "bidirectional"))
      (node (ref "R27") (pin "2") (pinfunction "2_2") (pintype "passive"))
      (node (ref "R29") (pin "2") (pinfunction "2_2") (pintype "passive"))
      (node (ref "VR1") (pin "4") (pinfunction "FB1_4") (pintype "bidirectional"))
    )
    (net (code "77") (name "Net-(C58-1)") (class "Default")
      (node (ref "C58") (pin "P$1") (pinfunction "1_P$1") (pintype "bidirectional"))
      (node (ref "U1") (pin "C1") (pinfunction "VDDS-SRAM_HV_SUP_C1") (pintype "bidirectional"))
    )
    (net (code "78") (name "Net-(C59-1)") (class "Default")
      (node (ref "C59") (pin "P$1") (pinfunction "1_P$1") (pintype "bidirectional"))
      (node (ref "U1") (pin "A3") (pinfunction "VDDC-CORE_A3") (pintype "bidirectional"))
    )
    (net (code "79") (name "Net-(C60-1)") (class "Default")
      (node (ref "C60") (pin "P$1") (pinfunction "1_P$1") (pintype "bidirectional"))
      (node (ref "U1") (pin "B3") (pinfunction "VDDC_LV-CORE_LV_B3") (pintype "bidirectional"))
    )
    (net (code "80") (name "Net-(C71-2)") (class "Default")
      (node (ref "C71") (pin "P$2") (pinfunction "2_P$2") (pintype "bidirectional"))
      (node (ref "U1") (pin "B10") (pinfunction "LPMICBIAS_B10") (pintype "output"))
    )
    (net (code "81") (name "Net-(C78-1)") (class "Default")
      (node (ref "C78") (pin "P$1") (pinfunction "1_P$1") (pintype "bidirectional"))
      (node (ref "RZ11") (pin "1") (pinfunction "1_1") (pintype "passive"))
      (node (ref "VR2") (pin "1") (pinfunction "OUT_1") (pintype "power_in"))
    )
    (net (code "82") (name "Net-(C79-2)") (class "Default")
      (node (ref "C79") (pin "P$2") (pinfunction "2_P$2") (pintype "bidirectional"))
      (node (ref "U1") (pin "A12") (pinfunction "LPADC_VREF_A12") (pintype "bidirectional"))
    )
    (net (code "83") (name "Net-(C91-1)") (class "Default")
      (node (ref "C91") (pin "P$1") (pinfunction "1_P$1") (pintype "bidirectional"))
      (node (ref "RZ4") (pin "1") (pinfunction "1_1") (pintype "passive"))
      (node (ref "VR3") (pin "1") (pinfunction "OUT_1") (pintype "power_in"))
    )
    (net (code "84") (name "Net-(D1-PadA1)") (class "Default")
      (node (ref "D1") (pin "A1") (pinfunction "A1_A1") (pintype "bidirectional"))
      (node (ref "D1") (pin "A2") (pinfunction "A2_A2") (pintype "bidirectional"))
      (node (ref "D2") (pin "A1") (pinfunction "A1_A1") (pintype "bidirectional"))
      (node (ref "D2") (pin "A2") (pinfunction "A2_A2") (pintype "bidirectional"))
      (node (ref "SJ1") (pin "1") (pinfunction "1_1") (pintype "passive"))
    )
    (net (code "85") (name "Net-(D1-PadC1)") (class "Default")
      (node (ref "D1") (pin "C1") (pinfunction "C1_C1") (pintype "bidirectional"))
      (node (ref "R5") (pin "1") (pinfunction "1_1") (pintype "passive"))
    )
    (net (code "86") (name "Net-(D1-PadC2)") (class "Default")
      (node (ref "D1") (pin "C2") (pinfunction "C2_C2") (pintype "bidirectional"))
      (node (ref "R2") (pin "1") (pinfunction "1_1") (pintype "passive"))
    )
    (net (code "87") (name "Net-(D2-PadC1)") (class "Default")
      (node (ref "D2") (pin "C1") (pinfunction "C1_C1") (pintype "bidirectional"))
      (node (ref "R4") (pin "1") (pinfunction "1_1") (pintype "passive"))
    )
    (net (code "88") (name "Net-(D2-PadC2)") (class "Default")
      (node (ref "D2") (pin "C2") (pinfunction "C2_C2") (pintype "bidirectional"))
      (node (ref "R3") (pin "1") (pinfunction "1_1") (pintype "passive"))
    )
    (net (code "89") (name "Net-(L1-1)") (class "Default")
      (node (ref "L1") (pin "P$1") (pinfunction "1_P$1") (pintype "bidirectional"))
      (node (ref "VR1") (pin "2") (pinfunction "LX2_2") (pintype "bidirectional"))
    )
    (net (code "90") (name "Net-(L2-2)") (class "Default")
      (node (ref "L2") (pin "P$2") (pinfunction "2_P$2") (pintype "bidirectional"))
      (node (ref "VR1") (pin "8") (pinfunction "LX1_8") (pintype "bidirectional"))
    )
    (net (code "91") (name "Net-(L4-1)") (class "Default")
      (node (ref "C17") (pin "2") (pinfunction "2_2") (pintype "bidirectional"))
      (node (ref "C18") (pin "2") (pinfunction "2_2") (pintype "bidirectional"))
      (node (ref "C19") (pin "2") (pinfunction "2_2") (pintype "bidirectional"))
      (node (ref "L4") (pin "P$1") (pinfunction "1_P$1") (pintype "bidirectional"))
    )
    (net (code "92") (name "Net-(L4-2)") (class "Default")
      (node (ref "C10") (pin "2") (pinfunction "2_2") (pintype "bidirectional"))
      (node (ref "C16") (pin "2") (pinfunction "2_2") (pintype "bidirectional"))
      (node (ref "C21") (pin "2") (pinfunction "2_2") (pintype "bidirectional"))
      (node (ref "C39") (pin "2") (pinfunction "2_2") (pintype "bidirectional"))
      (node (ref "C9") (pin "2") (pinfunction "2_2") (pintype "bidirectional"))
      (node (ref "L4") (pin "P$2") (pinfunction "2_P$2") (pintype "bidirectional"))
      (node (ref "U4") (pin "19") (pinfunction "AC2_19") (pintype "bidirectional"))
    )
    (net (code "93") (name "Net-(L5-1)") (class "Default")
      (node (ref "L5") (pin "P$1") (pinfunction "1_P$1") (pintype "bidirectional"))
      (node (ref "U1") (pin "A1") (pinfunction "SIMOBUCK_SW_A1") (pintype "bidirectional"))
    )
    (net (code "94") (name "Net-(L5-2)") (class "Default")
      (node (ref "L5") (pin "P$2") (pinfunction "2_P$2") (pintype "bidirectional"))
      (node (ref "U1") (pin "A2") (pinfunction "SIMOBUCK_SWSEL_A2") (pintype "bidirectional"))
    )
    (net (code "95") (name "Net-(LS1-N)") (class "Default")
      (node (ref "D4") (pin "ANODE") (pinfunction "ANODE_ANODE") (pintype "bidirectional"))
      (node (ref "LS1") (pin "-") (pinfunction "N_-") (pintype "passive"))
      (node (ref "Q2") (pin "D") (pinfunction "D_D") (pintype "passive"))
    )
    (net (code "96") (name "Net-(R6-Pad1)") (class "Default")
      (node (ref "R6") (pin "1") (pinfunction "1_1") (pintype "passive"))
      (node (ref "R7") (pin "2") (pinfunction "2_2") (pintype "passive"))
    )
    (net (code "97") (name "Net-(R8-Pad2)") (class "Default")
      (node (ref "R8") (pin "2") (pinfunction "2_2") (pintype "passive"))
      (node (ref "R9") (pin "1") (pinfunction "1_1") (pintype "passive"))
    )
    (net (code "98") (name "Net-(R13-Pad1)") (class "Default")
      (node (ref "R13") (pin "1") (pinfunction "1_1") (pintype "passive"))
      (node (ref "RX14") (pin "2") (pinfunction "2_2") (pintype "passive"))
    )
    (net (code "99") (name "Net-(R13-Pad2)") (class "Default")
      (node (ref "R13") (pin "2") (pinfunction "2_2") (pintype "passive"))
      (node (ref "RT1") (pin "1") (pinfunction "1_1") (pintype "passive"))
    )
    (net (code "100") (name "Net-(R18-Pad2)") (class "Default")
      (node (ref "R18") (pin "2") (pinfunction "2_2") (pintype "passive"))
      (node (ref "R23") (pin "1") (pinfunction "1_1") (pintype "passive"))
    )
    (net (code "101") (name "Net-(S3A-OUT)") (class "Default")
      (node (ref "C33") (pin "1") (pinfunction "1_1") (pintype "bidirectional"))
      (node (ref "RZ1") (pin "1") (pinfunction "1_1") (pintype "passive"))
      (node (ref "S3") (pin "8") (pinfunction "OUT_8") (pintype "bidirectional"))
    )
    (net (code "102") (name "Net-(S3B-OUT)") (class "Default")
      (node (ref "C25") (pin "1") (pinfunction "1_1") (pintype "bidirectional"))
      (node (ref "RZ2") (pin "1") (pinfunction "1_1") (pintype "passive"))
      (node (ref "S3") (pin "5") (pinfunction "OUT_5") (pintype "bidirectional"))
    )
    (net (code "103") (name "Net-(SJ2-Pad1)") (class "Default")
      (node (ref "SJ2") (pin "1") (pinfunction "1_1") (pintype "passive"))
      (node (ref "XR19") (pin "2") (pinfunction "2_2") (pintype "passive"))
    )
    (net (code "104") (name "Net-(TP0-TESTPOINT)") (class "Default")
      (node (ref "TP0") (pin "P$1") (pinfunction "TESTPOINT_P$1") (pintype "bidirectional"))
      (node (ref "U2") (pin "C2") (pinfunction "GPIO0/RXOKLED_C2") (pintype "bidirectional"))
    )
    (net (code "105") (name "Net-(TP1-TESTPOINT)") (class "Default")
      (node (ref "TP1") (pin "P$1") (pinfunction "TESTPOINT_P$1") (pintype "bidirectional"))
      (node (ref "U2") (pin "D3") (pinfunction "GPIO1/SFDLED_D3") (pintype "bidirectional"))
    )
    (net (code "106") (name "Net-(TP2-TESTPOINT)") (class "Default")
      (node (ref "TP2") (pin "P$1") (pinfunction "TESTPOINT_P$1") (pintype "bidirectional"))
      (node (ref "U2") (pin "E4") (pinfunction "GPIO2/RXLED_E4") (pintype "bidirectional"))
    )
    (net (code "107") (name "Net-(TP3-TESTPOINT)") (class "Default")
      (node (ref "TP3") (pin "P$1") (pinfunction "TESTPOINT_P$1") (pintype "bidirectional"))
      (node (ref "U2") (pin "E2") (pinfunction "GPIO3/TXLED_E2") (pintype "bidirectional"))
    )
    (net (code "108") (name "Net-(TP4-TESTPOINT)") (class "Default")
      (node (ref "TP4") (pin "P$1") (pinfunction "TESTPOINT_P$1") (pintype "bidirectional"))
      (node (ref "U2") (pin "F1") (pinfunction "GPIO4/EXTPA_F1") (pintype "bidirectional"))
    )
    (net (code "109") (name "Net-(TP5-TESTPOINT)") (class "Default")
      (node (ref "TP5") (pin "P$1") (pinfunction "TESTPOINT_P$1") (pintype "bidirectional"))
      (node (ref "U2") (pin "D1") (pinfunction "GPIO5/EXTTXE/SPIPOL_D1") (pintype "bidirectional"))
    )
    (net (code "110") (name "Net-(U1-RFIOP)") (class "Default")
      (node (ref "CX5") (pin "1") (pinfunction "1_1") (pintype "passive"))
      (node (ref "L7") (pin "1") (pinfunction "1_1") (pintype "passive"))
      (node (ref "U1") (pin "M2") (pinfunction "RFIOP_M2") (pintype "bidirectional"))
    )
    (net (code "111") (name "Net-(U1-VDDBH_SW--BLE_BUCK_SW)") (class "Default")
      (node (ref "L6") (pin "1") (pinfunction "1_1") (pintype "bidirectional"))
      (node (ref "U1") (pin "H12") (pinfunction "VDDBH_SW--BLE_BUCK_SW_H12") (pintype "bidirectional"))
    )
    (net (code "112") (name "Net-(U1-XI)") (class "Default")
      (node (ref "C81") (pin "1") (pinfunction "1_1") (pintype "passive"))
      (node (ref "U1") (pin "A4") (pinfunction "XI_A4") (pintype "bidirectional"))
      (node (ref "X3") (pin "2") (pinfunction "2_2") (pintype "bidirectional"))
    )
    (net (code "113") (name "Net-(U1-XI32M)") (class "Default")
      (node (ref "CX4") (pin "1") (pinfunction "1_1") (pintype "passive"))
      (node (ref "U1") (pin "C12") (pinfunction "XI32M_C12") (pintype "bidirectional"))
      (node (ref "X1") (pin "3") (pinfunction "2_3") (pintype "bidirectional"))
    )
    (net (code "114") (name "Net-(U1-XO)") (class "Default")
      (node (ref "C80") (pin "1") (pinfunction "1_1") (pintype "passive"))
      (node (ref "U1") (pin "A5") (pinfunction "XO_A5") (pintype "bidirectional"))
      (node (ref "X3") (pin "1") (pinfunction "1_1") (pintype "bidirectional"))
    )
    (net (code "115") (name "Net-(U1-XO32M)") (class "Default")
      (node (ref "CX3") (pin "1") (pinfunction "1_1") (pintype "passive"))
      (node (ref "U1") (pin "D12") (pinfunction "XO32M_D12") (pintype "bidirectional"))
      (node (ref "X1") (pin "1") (pinfunction "1_1") (pintype "bidirectional"))
    )
    (net (code "116") (name "Net-(U2-RF2)") (class "Default")
      (node (ref "R1") (pin "1") (pinfunction "1_1") (pintype "passive"))
      (node (ref "U2") (pin "H5") (pinfunction "RF2_H5") (pintype "bidirectional"))
    )
    (net (code "117") (name "Net-(U2-VDD2A)") (class "Default")
      (node (ref "C12") (pin "P$1") (pinfunction "P$1_P$1") (pintype "bidirectional"))
      (node (ref "FB1") (pin "P$2") (pinfunction "P$2_P$2") (pintype "bidirectional"))
      (node (ref "U2") (pin "F15") (pinfunction "VDD2A_F15") (pintype "bidirectional"))
    )
    (net (code "118") (name "Net-(U2-VIO_D)") (class "Default")
      (node (ref "C23") (pin "1") (pinfunction "1_1") (pintype "bidirectional"))
      (node (ref "U2") (pin "A4") (pinfunction "VIO_D_A4") (pintype "bidirectional"))
    )
    (net (code "119") (name "Net-(U2-VTX_D)") (class "Default")
      (node (ref "C37") (pin "P$2") (pinfunction "P$2_P$2") (pintype "bidirectional"))
      (node (ref "U2") (pin "C14") (pinfunction "VTX_D_C14") (pintype "bidirectional"))
    )
    (net (code "120") (name "Net-(U2-XTI)") (class "Default")
      (node (ref "C3") (pin "P$1") (pinfunction "P$1_P$1") (pintype "bidirectional"))
      (node (ref "U2") (pin "H15") (pinfunction "XTI_H15") (pintype "bidirectional"))
      (node (ref "X4") (pin "1") (pinfunction "1_1") (pintype "bidirectional"))
    )
    (net (code "121") (name "Net-(U2-XTO)") (class "Default")
      (node (ref "C4") (pin "P$1") (pinfunction "P$1_P$1") (pintype "bidirectional"))
      (node (ref "U2") (pin "G14") (pinfunction "XTO_G14") (pintype "bidirectional"))
      (node (ref "X4") (pin "3") (pinfunction "2_3") (pintype "bidirectional"))
    )
    (net (code "122") (name "Net-(U3-ISET)") (class "Default")
      (node (ref "R15") (pin "2") (pinfunction "2_2") (pintype "passive"))
      (node (ref "U3") (pin "2") (pinfunction "ISET_2") (pintype "bidirectional"))
    )
    (net (code "123") (name "Net-(U3-PRETERM)") (class "Default")
      (node (ref "RX7") (pin "2") (pinfunction "2_2") (pintype "passive"))
      (node (ref "U3") (pin "4") (pinfunction "PRETERM_4") (pintype "bidirectional"))
    )
    (net (code "124") (name "Net-(U4-AC1)") (class "Default")
      (node (ref "C10") (pin "1") (pinfunction "1_1") (pintype "bidirectional"))
      (node (ref "C15") (pin "2") (pinfunction "2_2") (pintype "bidirectional"))
      (node (ref "C17") (pin "1") (pinfunction "1_1") (pintype "bidirectional"))
      (node (ref "C18") (pin "1") (pinfunction "1_1") (pintype "bidirectional"))
      (node (ref "C19") (pin "1") (pinfunction "1_1") (pintype "bidirectional"))
      (node (ref "C20") (pin "2") (pinfunction "2_2") (pintype "bidirectional"))
      (node (ref "C38") (pin "2") (pinfunction "2_2") (pintype "bidirectional"))
      (node (ref "C9") (pin "1") (pinfunction "1_1") (pintype "bidirectional"))
      (node (ref "U4") (pin "2") (pinfunction "AC1_2") (pintype "bidirectional"))
    )
    (net (code "125") (name "Net-(U4-BOOT1)") (class "Default")
      (node (ref "C15") (pin "1") (pinfunction "1_1") (pintype "bidirectional"))
      (node (ref "U4") (pin "3") (pinfunction "BOOT1_3") (pintype "bidirectional"))
    )
    (net (code "126") (name "Net-(U4-BOOT2)") (class "Default")
      (node (ref "C16") (pin "1") (pinfunction "1_1") (pintype "bidirectional"))
      (node (ref "U4") (pin "17") (pinfunction "BOOT2_17") (pintype "bidirectional"))
    )
    (net (code "127") (name "Net-(U4-CLAMP1)") (class "Default")
      (node (ref "C38") (pin "1") (pinfunction "1_1") (pintype "bidirectional"))
      (node (ref "U4") (pin "5") (pinfunction "CLAMP1_5") (pintype "bidirectional"))
    )
    (net (code "128") (name "Net-(U4-CLAMP2)") (class "Default")
      (node (ref "C39") (pin "1") (pinfunction "1_1") (pintype "bidirectional"))
      (node (ref "U4") (pin "16") (pinfunction "CLAMP2_16") (pintype "bidirectional"))
    )
    (net (code "129") (name "Net-(U4-COMM1)") (class "Default")
      (node (ref "C20") (pin "1") (pinfunction "1_1") (pintype "bidirectional"))
      (node (ref "U4") (pin "6") (pinfunction "COMM1_6") (pintype "bidirectional"))
    )
    (net (code "130") (name "Net-(U4-COMM2)") (class "Default")
      (node (ref "C21") (pin "1") (pinfunction "1_1") (pintype "bidirectional"))
      (node (ref "U4") (pin "15") (pinfunction "COMM2_15") (pintype "bidirectional"))
    )
    (net (code "131") (name "Net-(U4-FOD)") (class "Default")
      (node (ref "R23") (pin "2") (pinfunction "2_2") (pintype "passive"))
      (node (ref "R7") (pin "1") (pinfunction "1_1") (pintype "passive"))
      (node (ref "R9") (pin "2") (pinfunction "2_2") (pintype "passive"))
      (node (ref "U4") (pin "14") (pinfunction "FOD_14") (pintype "bidirectional"))
    )
    (net (code "132") (name "Net-(U4-ILIM)") (class "Default")
      (node (ref "R8") (pin "1") (pinfunction "1_1") (pintype "passive"))
      (node (ref "U4") (pin "12") (pinfunction "ILIM_12") (pintype "bidirectional"))
    )
    (net (code "133") (name "Net-(U4-RECT)") (class "Default")
      (node (ref "C28") (pin "1") (pinfunction "1_1") (pintype "bidirectional"))
      (node (ref "C56") (pin "1") (pinfunction "1_1") (pintype "bidirectional"))
      (node (ref "C57") (pin "1") (pinfunction "1_1") (pintype "bidirectional"))
      (node (ref "R18") (pin "1") (pinfunction "1_1") (pintype "passive"))
      (node (ref "U4") (pin "18") (pinfunction "RECT_18") (pintype "bidirectional"))
    )
    (net (code "134") (name "Net-(U6-CAP)") (class "Default")
      (node (ref "C36") (pin "1") (pinfunction "1_1") (pintype "bidirectional"))
      (node (ref "U6") (pin "9") (pinfunction "CAP_9") (pintype "bidirectional"))
    )
    (net (code "135") (name "Net-(U6-PS1)") (class "Default")
      (node (ref "SJ7") (pin "2") (pinfunction "2_2") (pintype "passive"))
      (node (ref "U6") (pin "5") (pinfunction "PS1_5") (pintype "input"))
    )
    (net (code "136") (name "Net-(U7-VCTRL)") (class "Default")
      (node (ref "SJ3") (pin "2") (pinfunction "2_2") (pintype "passive"))
      (node (ref "U7") (pin "8") (pinfunction "VCTRL_8") (pintype "bidirectional"))
    )
    (net (code "137") (name "Net-(U7-VDD)") (class "Default")
      (node (ref "C11") (pin "P$1") (pinfunction "P$1_P$1") (pintype "bidirectional"))
      (node (ref "C43") (pin "P$1") (pinfunction "P$1_P$1") (pintype "bidirectional"))
      (node (ref "RZ4") (pin "2") (pinfunction "2_2") (pintype "passive"))
      (node (ref "U7") (pin "1") (pinfunction "VDD_1") (pintype "bidirectional"))
    )
    (net (code "138") (name "Net-(VR2-EN)") (class "Default")
      (node (ref "RZ10") (pin "2") (pinfunction "2_2") (pintype "passive"))
      (node (ref "VR2") (pin "3") (pinfunction "EN_3") (pintype "input"))
    )
    (net (code "139") (name "Net-(XJ1-CC1)") (class "Default")
      (node (ref "XJ1") (pin "A5") (pinfunction "CC1_A5") (pintype "bidirectional"))
      (node (ref "XR16") (pin "1") (pinfunction "1_1") (pintype "passive"))
    )
    (net (code "140") (name "Net-(XJ1-CC2)") (class "Default")
      (node (ref "XJ1") (pin "B5") (pinfunction "CC2_B5") (pintype "bidirectional"))
      (node (ref "XR17") (pin "1") (pinfunction "1_1") (pintype "passive"))
    )
    (net (code "141") (name "RF1") (class "Default")
      (node (ref "S2") (pin "9") (pinfunction "J2_9") (pintype "bidirectional"))
      (node (ref "U7") (pin "6") (pinfunction "LNA_OUT_6") (pintype "bidirectional"))
    )
    (net (code "142") (name "RF2") (class "Default")
      (node (ref "A2") (pin "FEED") (pinfunction "ANTENNA_FEED") (pintype "bidirectional"))
      (node (ref "S2") (pin "3") (pinfunction "J3_3") (pintype "bidirectional"))
    )
    (net (code "143") (name "RF3") (class "Default")
      (node (ref "A3") (pin "FEED") (pinfunction "ANTENNA_FEED") (pintype "bidirectional"))
      (node (ref "S2") (pin "1") (pinfunction "J1_1") (pintype "bidirectional"))
      (node (ref "S4") (pin "IN") (pinfunction "IN_IN") (pintype "bidirectional"))
      (node (ref "S4") (pin "OUT") (pinfunction "A_OUT") (pintype "bidirectional"))
    )
    (net (code "144") (name "VBAT") (class "Default")
      (node (ref "C42") (pin "1") (pinfunction "1_1") (pintype "bidirectional"))
      (node (ref "J3") (pin "1") (pinfunction "1_1") (pintype "passive"))
      (node (ref "J4") (pin "3") (pinfunction "3_3") (pintype "bidirectional"))
      (node (ref "J4") (pin "3SUPP") (pinfunction "3_3SUPP") (pintype "bidirectional"))
      (node (ref "S1") (pin "2") (pinfunction "2_2") (pintype "passive"))
      (node (ref "U3") (pin "10") (pinfunction "OUT_10") (pintype "bidirectional"))
    )
    (net (code "145") (name "VBAT_SWITCHED") (class "Default")
      (node (ref "C45") (pin "2") (pinfunction "2_2") (pintype "bidirectional"))
      (node (ref "C48") (pin "1") (pinfunction "1_1") (pintype "bidirectional"))
      (node (ref "R31") (pin "2") (pinfunction "2_2") (pintype "passive"))
      (node (ref "R33") (pin "1") (pinfunction "1_1") (pintype "passive"))
      (node (ref "R34") (pin "1") (pinfunction "1_1") (pintype "passive"))
      (node (ref "S1") (pin "3") (pinfunction "3_3") (pintype "passive"))
      (node (ref "VR1") (pin "1") (pinfunction "VIN2_1") (pintype "bidirectional"))
      (node (ref "VR1") (pin "7") (pinfunction "VIN1_7") (pintype "bidirectional"))
    )
    (net (code "146") (name "VDDAUDA_1P8-CLEAN") (class "Default")
      (node (ref "C72") (pin "P$1") (pinfunction "1_P$1") (pintype "bidirectional"))
      (node (ref "RZ11") (pin "2") (pinfunction "2_2") (pintype "passive"))
      (node (ref "U1") (pin "B11") (pinfunction "VDDAUDA_B11") (pintype "bidirectional"))
    )
    (net (code "147") (name "VQI") (class "Default")
      (node (ref "C29") (pin "1") (pinfunction "1_1") (pintype "bidirectional"))
      (node (ref "C41") (pin "1") (pinfunction "1_1") (pintype "bidirectional"))
      (node (ref "C53") (pin "1") (pinfunction "1_1") (pintype "bidirectional"))
      (node (ref "Q1") (pin "A2") (pinfunction "D1_A2") (pintype "bidirectional"))
      (node (ref "Q1") (pin "A3") (pinfunction "D1_A3") (pintype "bidirectional"))
      (node (ref "Q1") (pin "B3") (pinfunction "D1_B3") (pintype "bidirectional"))
      (node (ref "U3") (pin "1") (pinfunction "IN_1") (pintype "bidirectional"))
      (node (ref "U4") (pin "4") (pinfunction "OUT_4") (pintype "bidirectional"))
    )
    (net (code "148") (name "VR1_1P8_EN") (class "Default")
      (node (ref "R34") (pin "2") (pinfunction "2_2") (pintype "passive"))
      (node (ref "VR1") (pin "6") (pinfunction "EN1_6") (pintype "bidirectional"))
    )
    (net (code "149") (name "VR1_2P5_EN") (class "Default")
      (node (ref "R33") (pin "2") (pinfunction "2_2") (pintype "passive"))
      (node (ref "VR1") (pin "12") (pinfunction "EN2_12") (pintype "bidirectional"))
    )
    (net (code "150") (name "VUSB") (class "Default")
      (node (ref "C40") (pin "2") (pinfunction "2_2") (pintype "bidirectional"))
      (node (ref "Q1") (pin "B2") (pinfunction "D2_B2") (pintype "bidirectional"))
      (node (ref "Q1") (pin "C2") (pinfunction "D2_C2") (pintype "bidirectional"))
      (node (ref "Q1") (pin "C3") (pinfunction "D2_C3") (pintype "bidirectional"))
      (node (ref "U4") (pin "9") (pinfunction "AD_9") (pintype "bidirectional"))
      (node (ref "XJ1") (pin "A4/B9") (pinfunction "VBUS_A4/B9") (pintype "power_in"))
      (node (ref "XJ1") (pin "B4/A9") (pinfunction "VBUS_B4/A9") (pintype "power_in"))
    )
    (net (code "151") (name "unconnected-(Q1-S-PadB1)") (class "Default")
      (node (ref "Q1") (pin "B1") (pinfunction "S_B1") (pintype "bidirectional"))
    )
    (net (code "152") (name "unconnected-(S1-Pad1)") (class "Default")
      (node (ref "S1") (pin "1") (pinfunction "1_1") (pintype "passive"))
    )
    (net (code "153") (name "unconnected-(U1-GPIO0-PadH3)") (class "Default")
      (node (ref "U1") (pin "H3") (pinfunction "GPIO0_H3") (pintype "bidirectional"))
    )
    (net (code "154") (name "unconnected-(U1-GPIO1-PadJ4)") (class "Default")
      (node (ref "U1") (pin "J4") (pinfunction "GPIO1_J4") (pintype "bidirectional"))
    )
    (net (code "155") (name "unconnected-(U1-GPIO2-PadK4)") (class "Default")
      (node (ref "U1") (pin "K4") (pinfunction "GPIO2_K4") (pintype "bidirectional"))
    )
    (net (code "156") (name "unconnected-(U1-GPIO4-PadM4)") (class "Default")
      (node (ref "U1") (pin "M4") (pinfunction "GPIO4_M4") (pintype "bidirectional"))
    )
    (net (code "157") (name "unconnected-(U1-GPIO5-PadH4)") (class "Default")
      (node (ref "U1") (pin "H4") (pinfunction "GPIO5_H4") (pintype "bidirectional"))
    )
    (net (code "158") (name "unconnected-(U1-GPIO7-PadJ6)") (class "Default")
      (node (ref "U1") (pin "J6") (pinfunction "GPIO7_J6") (pintype "bidirectional"))
    )
    (net (code "159") (name "unconnected-(U1-GPIO11-PadE4)") (class "Default")
      (node (ref "U1") (pin "E4") (pinfunction "GPIO11_E4") (pintype "bidirectional"))
    )
    (net (code "160") (name "unconnected-(U1-GPIO12-PadB4)") (class "Default")
      (node (ref "U1") (pin "B4") (pinfunction "GPIO12_B4") (pintype "bidirectional"))
    )
    (net (code "161") (name "unconnected-(U1-GPIO15-PadE5)") (class "Default")
      (node (ref "U1") (pin "E5") (pinfunction "GPIO15_E5") (pintype "bidirectional"))
    )
    (net (code "162") (name "unconnected-(U1-GPIO16-PadD7)") (class "Default")
      (node (ref "U1") (pin "D7") (pinfunction "GPIO16_D7") (pintype "bidirectional"))
    )
    (net (code "163") (name "unconnected-(U1-GPIO19-PadC3)") (class "Default")
      (node (ref "U1") (pin "C3") (pinfunction "GPIO19_C3") (pintype "bidirectional"))
    )
    (net (code "164") (name "unconnected-(U1-GPIO22-PadF3)") (class "Default")
      (node (ref "U1") (pin "F3") (pinfunction "GPIO22_F3") (pintype "bidirectional"))
    )
    (net (code "165") (name "unconnected-(U1-GPIO23-PadF2)") (class "Default")
      (node (ref "U1") (pin "F2") (pinfunction "GPIO23_F2") (pintype "bidirectional"))
    )
    (net (code "166") (name "unconnected-(U1-GPIO28-PadE3)") (class "Default")
      (node (ref "U1") (pin "E3") (pinfunction "GPIO28_E3") (pintype "bidirectional"))
    )
    (net (code "167") (name "unconnected-(U1-GPIO29-PadF4)") (class "Default")
      (node (ref "U1") (pin "F4") (pinfunction "GPIO29_F4") (pintype "bidirectional"))
    )
    (net (code "168") (name "unconnected-(U1-GPIO37-PadF11)") (class "Default")
      (node (ref "U1") (pin "F11") (pinfunction "GPIO37_F11") (pintype "bidirectional"))
    )
    (net (code "169") (name "unconnected-(U1-GPIO52-PadC10)") (class "Default")
      (node (ref "U1") (pin "C10") (pinfunction "GPIO52_C10") (pintype "bidirectional"))
    )
    (net (code "170") (name "unconnected-(U1-GPIO54-PadD10)") (class "Default")
      (node (ref "U1") (pin "D10") (pinfunction "GPIO54_D10") (pintype "bidirectional"))
    )
    (net (code "171") (name "unconnected-(U1-GPIO56-PadE10)") (class "Default")
      (node (ref "U1") (pin "E10") (pinfunction "GPIO56_E10") (pintype "bidirectional"))
    )
    (net (code "172") (name "unconnected-(U1-GPIO57-PadE9)") (class "Default")
      (node (ref "U1") (pin "E9") (pinfunction "GPIO57_E9") (pintype "bidirectional"))
    )
    (net (code "173") (name "unconnected-(U1-GPIO59-PadJ8)") (class "Default")
      (node (ref "U1") (pin "J8") (pinfunction "GPIO59_J8") (pintype "bidirectional"))
    )
    (net (code "174") (name "unconnected-(U1-GPIO61-PadK6)") (class "Default")
      (node (ref "U1") (pin "K6") (pinfunction "GPIO61_K6") (pintype "bidirectional"))
    )
    (net (code "175") (name "unconnected-(U1-GPIO62-PadL6)") (class "Default")
      (node (ref "U1") (pin "L6") (pinfunction "GPIO62_L6") (pintype "bidirectional"))
    )
    (net (code "176") (name "unconnected-(U1-GPIO64-PadB6)") (class "Default")
      (node (ref "U1") (pin "B6") (pinfunction "GPIO64_B6") (pintype "bidirectional"))
    )
    (net (code "177") (name "unconnected-(U1-GPIO67-PadC6)") (class "Default")
      (node (ref "U1") (pin "C6") (pinfunction "GPIO67_C6") (pintype "bidirectional"))
    )
    (net (code "178") (name "unconnected-(U1-GPIO68-PadB7)") (class "Default")
      (node (ref "U1") (pin "B7") (pinfunction "GPIO68_B7") (pintype "bidirectional"))
    )
    (net (code "179") (name "unconnected-(U1-GPIO70-PadC5)") (class "Default")
      (node (ref "U1") (pin "C5") (pinfunction "GPIO70_C5") (pintype "bidirectional"))
    )
    (net (code "180") (name "unconnected-(U1-GPIO71-PadC7)") (class "Default")
      (node (ref "U1") (pin "C7") (pinfunction "GPIO71_C7") (pintype "bidirectional"))
    )
    (net (code "181") (name "unconnected-(U1-GPIO73-PadD8)") (class "Default")
      (node (ref "U1") (pin "D8") (pinfunction "GPIO73_D8") (pintype "bidirectional"))
    )
    (net (code "182") (name "unconnected-(U1-GPIO74-PadG11)") (class "Default")
      (node (ref "U1") (pin "G11") (pinfunction "GPIO74_G11") (pintype "bidirectional"))
    )
    (net (code "183") (name "unconnected-(U1-GPIO75-PadH11)") (class "Default")
      (node (ref "U1") (pin "H11") (pinfunction "GPIO75_H11") (pintype "bidirectional"))
    )
    (net (code "184") (name "unconnected-(U1-GPIO76-PadJ11)") (class "Default")
      (node (ref "U1") (pin "J11") (pinfunction "GPIO76_J11") (pintype "bidirectional"))
    )
    (net (code "185") (name "unconnected-(U1-GPIO77-PadK11)") (class "Default")
      (node (ref "U1") (pin "K11") (pinfunction "GPIO77_K11") (pintype "bidirectional"))
    )
    (net (code "186") (name "unconnected-(U1-GPIO78-PadL11)") (class "Default")
      (node (ref "U1") (pin "L11") (pinfunction "GPIO78_L11") (pintype "bidirectional"))
    )
    (net (code "187") (name "unconnected-(U1-GPIO84-PadJ9)") (class "Default")
      (node (ref "U1") (pin "J9") (pinfunction "GPIO84_J9") (pintype "bidirectional"))
    )
    (net (code "188") (name "unconnected-(U1-GPIO85-PadH9)") (class "Default")
      (node (ref "U1") (pin "H9") (pinfunction "GPIO85_H9") (pintype "bidirectional"))
    )
    (net (code "189") (name "unconnected-(U1-GPIO86-PadG10)") (class "Default")
      (node (ref "U1") (pin "G10") (pinfunction "GPIO86_G10") (pintype "bidirectional"))
    )
    (net (code "190") (name "unconnected-(U1-GPIO87-PadG9)") (class "Default")
      (node (ref "U1") (pin "G9") (pinfunction "GPIO87_G9") (pintype "bidirectional"))
    )
    (net (code "191") (name "unconnected-(U1-GPIO89-PadF10)") (class "Default")
      (node (ref "U1") (pin "F10") (pinfunction "GPIO89_F10") (pintype "bidirectional"))
    )
    (net (code "192") (name "unconnected-(U1-GPIO90-PadJ2)") (class "Default")
      (node (ref "U1") (pin "J2") (pinfunction "GPIO90_J2") (pintype "bidirectional"))
    )
    (net (code "193") (name "unconnected-(U1-GPIO91-PadK2)") (class "Default")
      (node (ref "U1") (pin "K2") (pinfunction "GPIO91_K2") (pintype "bidirectional"))
    )
    (net (code "194") (name "unconnected-(U1-LPADC_D0NSE0-PadA10)") (class "Default")
      (node (ref "U1") (pin "A10") (pinfunction "LPADC_D0NSE0_A10") (pintype "input"))
    )
    (net (code "195") (name "unconnected-(U1-LPADC_D0PSE1-PadA11)") (class "Default")
      (node (ref "U1") (pin "A11") (pinfunction "LPADC_D0PSE1_A11") (pintype "input"))
    )
    (net (code "196") (name "unconnected-(U1-LPADC_D1NSE2-PadC11)") (class "Default")
      (node (ref "U1") (pin "C11") (pinfunction "LPADC_D1NSE2_C11") (pintype "input"))
    )
    (net (code "197") (name "unconnected-(U1-LPADC_D1PSE3-PadD11)") (class "Default")
      (node (ref "U1") (pin "D11") (pinfunction "LPADC_D1PSE3_D11") (pintype "input"))
    )
    (net (code "198") (name "unconnected-(U1-MIPI_CLKN-PadJ12)") (class "Default")
      (node (ref "U1") (pin "J12") (pinfunction "MIPI_CLKN_J12") (pintype "bidirectional"))
    )
    (net (code "199") (name "unconnected-(U1-MIPI_CLKP-PadK12)") (class "Default")
      (node (ref "U1") (pin "K12") (pinfunction "MIPI_CLKP_K12") (pintype "bidirectional"))
    )
    (net (code "200") (name "unconnected-(U1-MIPI_DON-PadL12)") (class "Default")
      (node (ref "U1") (pin "L12") (pinfunction "MIPI_DON_L12") (pintype "bidirectional"))
    )
    (net (code "201") (name "unconnected-(U1-MIPI_DOP-PadM12)") (class "Default")
      (node (ref "U1") (pin "M12") (pinfunction "MIPI_DOP_M12") (pintype "bidirectional"))
    )
    (net (code "202") (name "unconnected-(U1-TXEN-PadK1)") (class "Default")
      (node (ref "U1") (pin "K1") (pinfunction "TXEN_K1") (pintype "output"))
    )
    (net (code "203") (name "unconnected-(VR1-NC1-Pad5)") (class "Default")
      (node (ref "VR1") (pin "5") (pinfunction "NC1_5") (pintype "bidirectional"))
    )
    (net (code "204") (name "unconnected-(VR1-NC2-Pad11)") (class "Default")
      (node (ref "VR1") (pin "11") (pinfunction "NC2_11") (pintype "bidirectional"))
    )
    (net (code "205") (name "unconnected-(XJ1-SBU1-PadA8)") (class "Default")
      (node (ref "XJ1") (pin "A8") (pinfunction "SBU1_A8") (pintype "bidirectional"))
    )
    (net (code "206") (name "unconnected-(XJ1-SBU2-PadB8)") (class "Default")
      (node (ref "XJ1") (pin "B8") (pinfunction "SBU2_B8") (pintype "bidirectional"))
    )
    (net (code "207") (name "~{AD_EN}") (class "Default")
      (node (ref "Q1") (pin "A1") (pinfunction "G1_A1") (pintype "input"))
      (node (ref "Q1") (pin "C1") (pinfunction "G2_C1") (pintype "input"))
      (node (ref "U4") (pin "8") (pinfunction "~{AD-EN}_8") (pintype "bidirectional"))
    )
  )
)
